# SMP.net
KiCad netlist of a schematic drawn in EAGLE
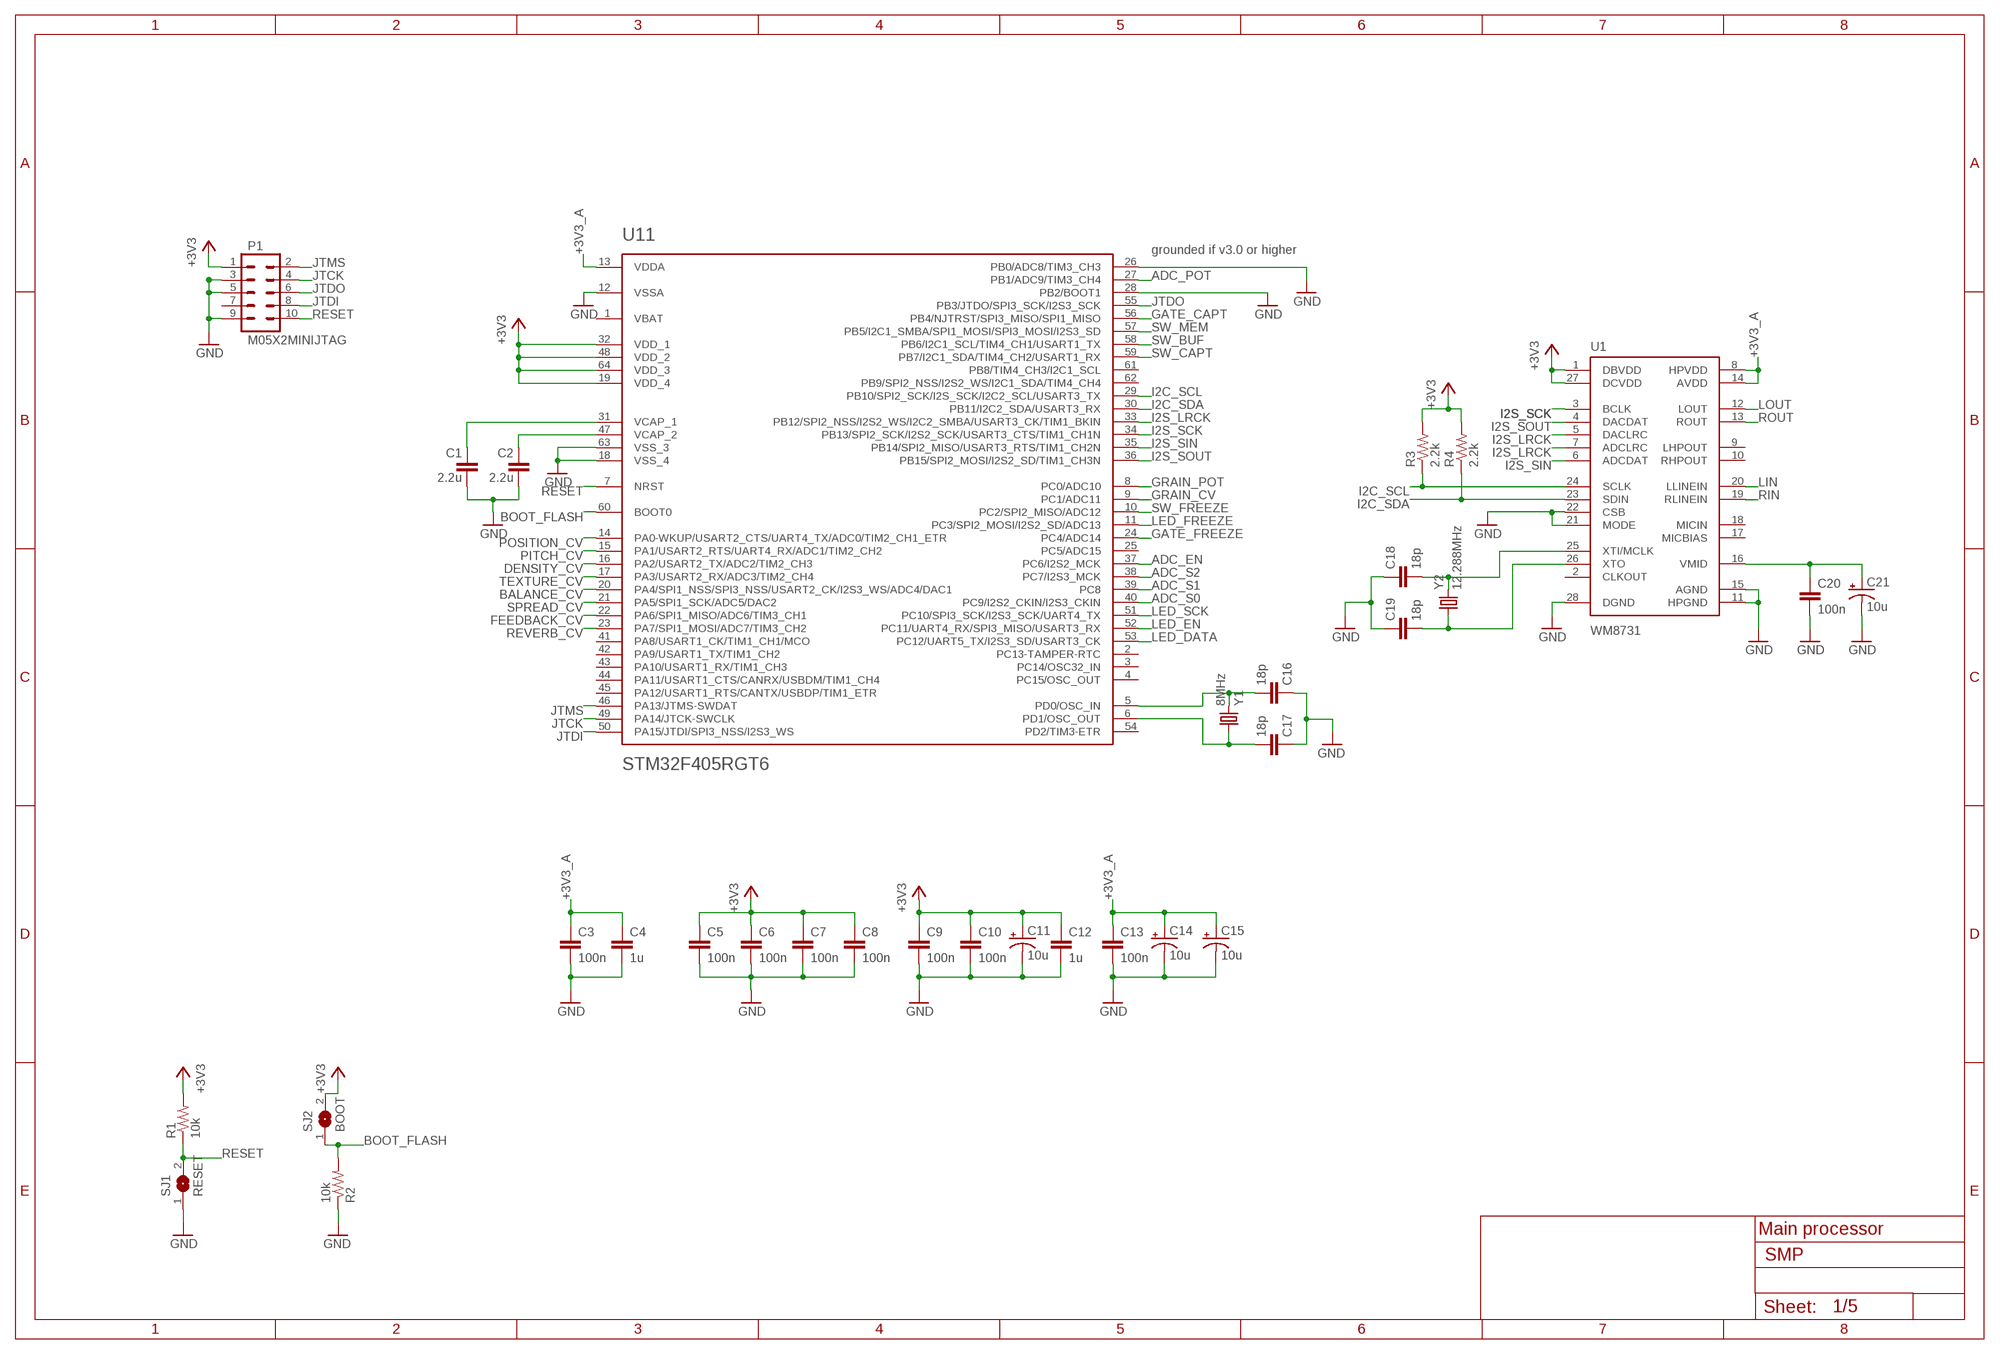
[diagram p0: schematic, sheet 1]
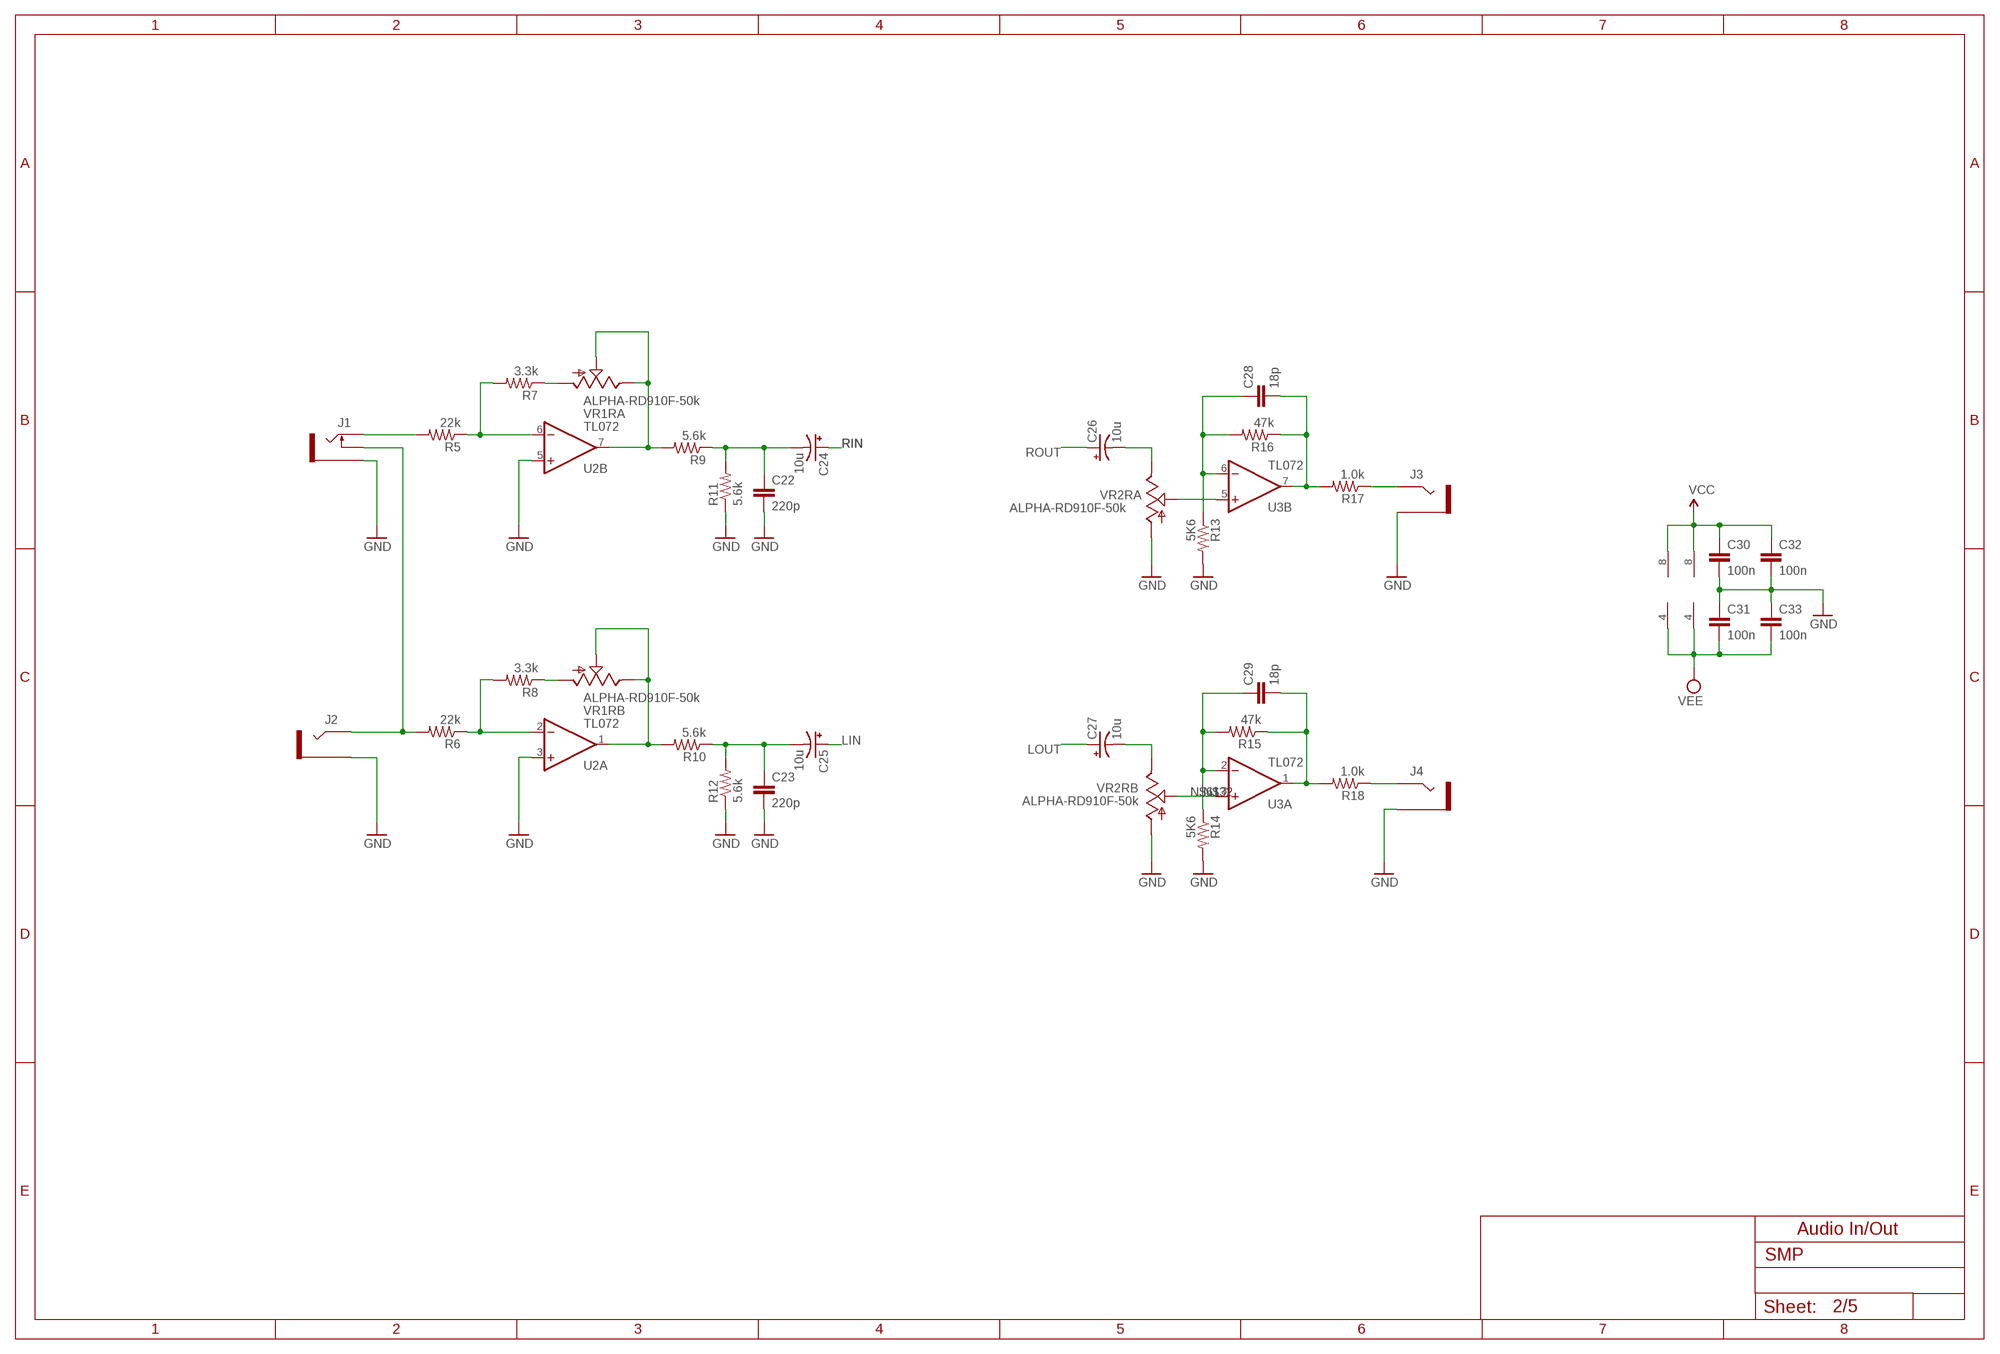
[diagram p1: schematic, sheet 2]
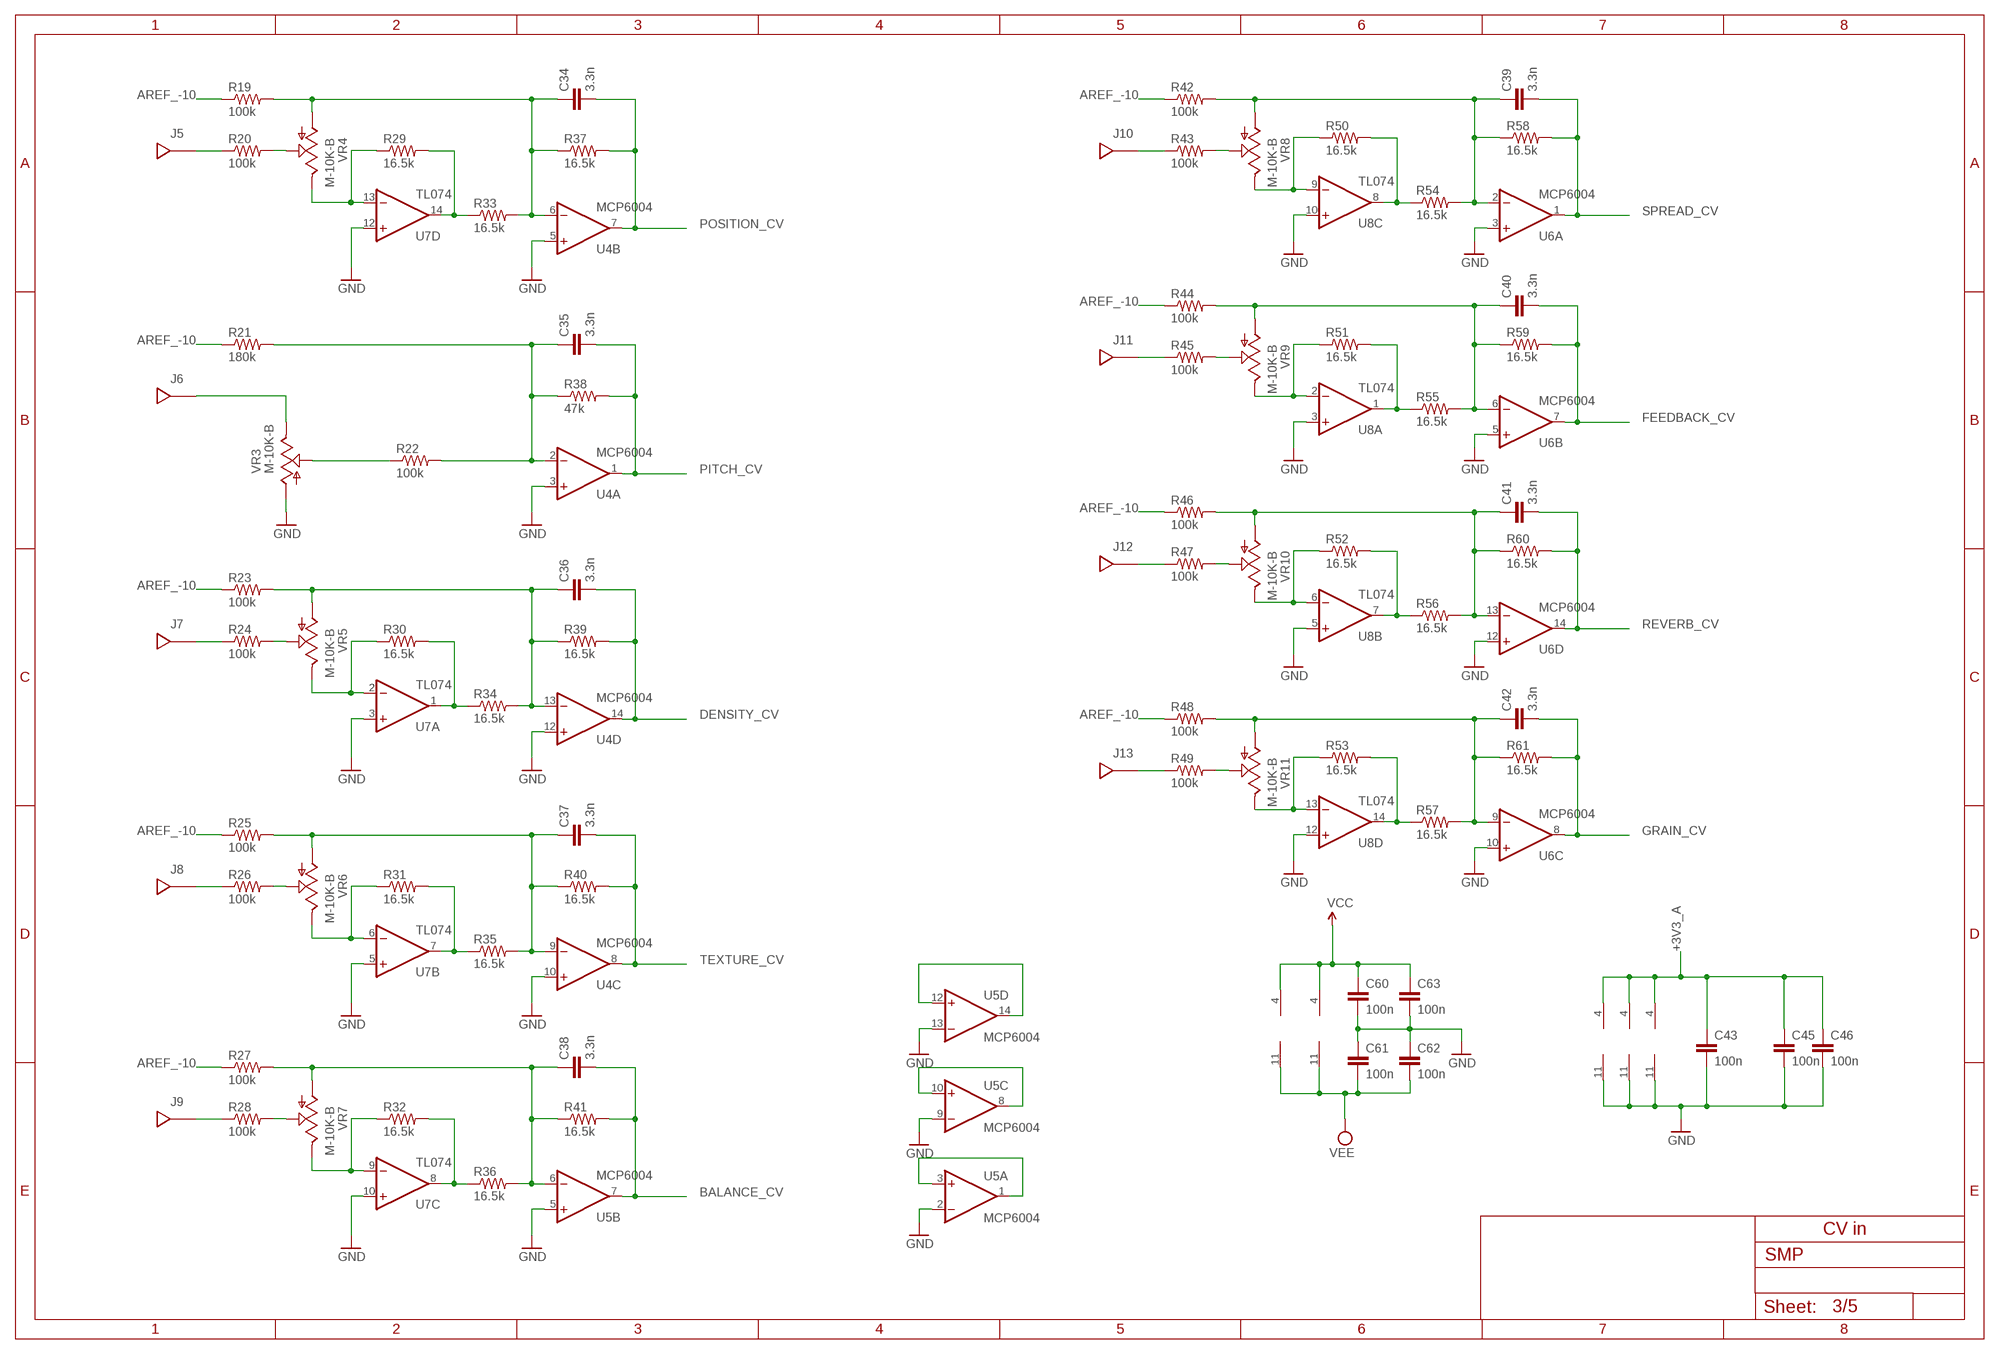
[diagram p2: schematic, sheet 3]
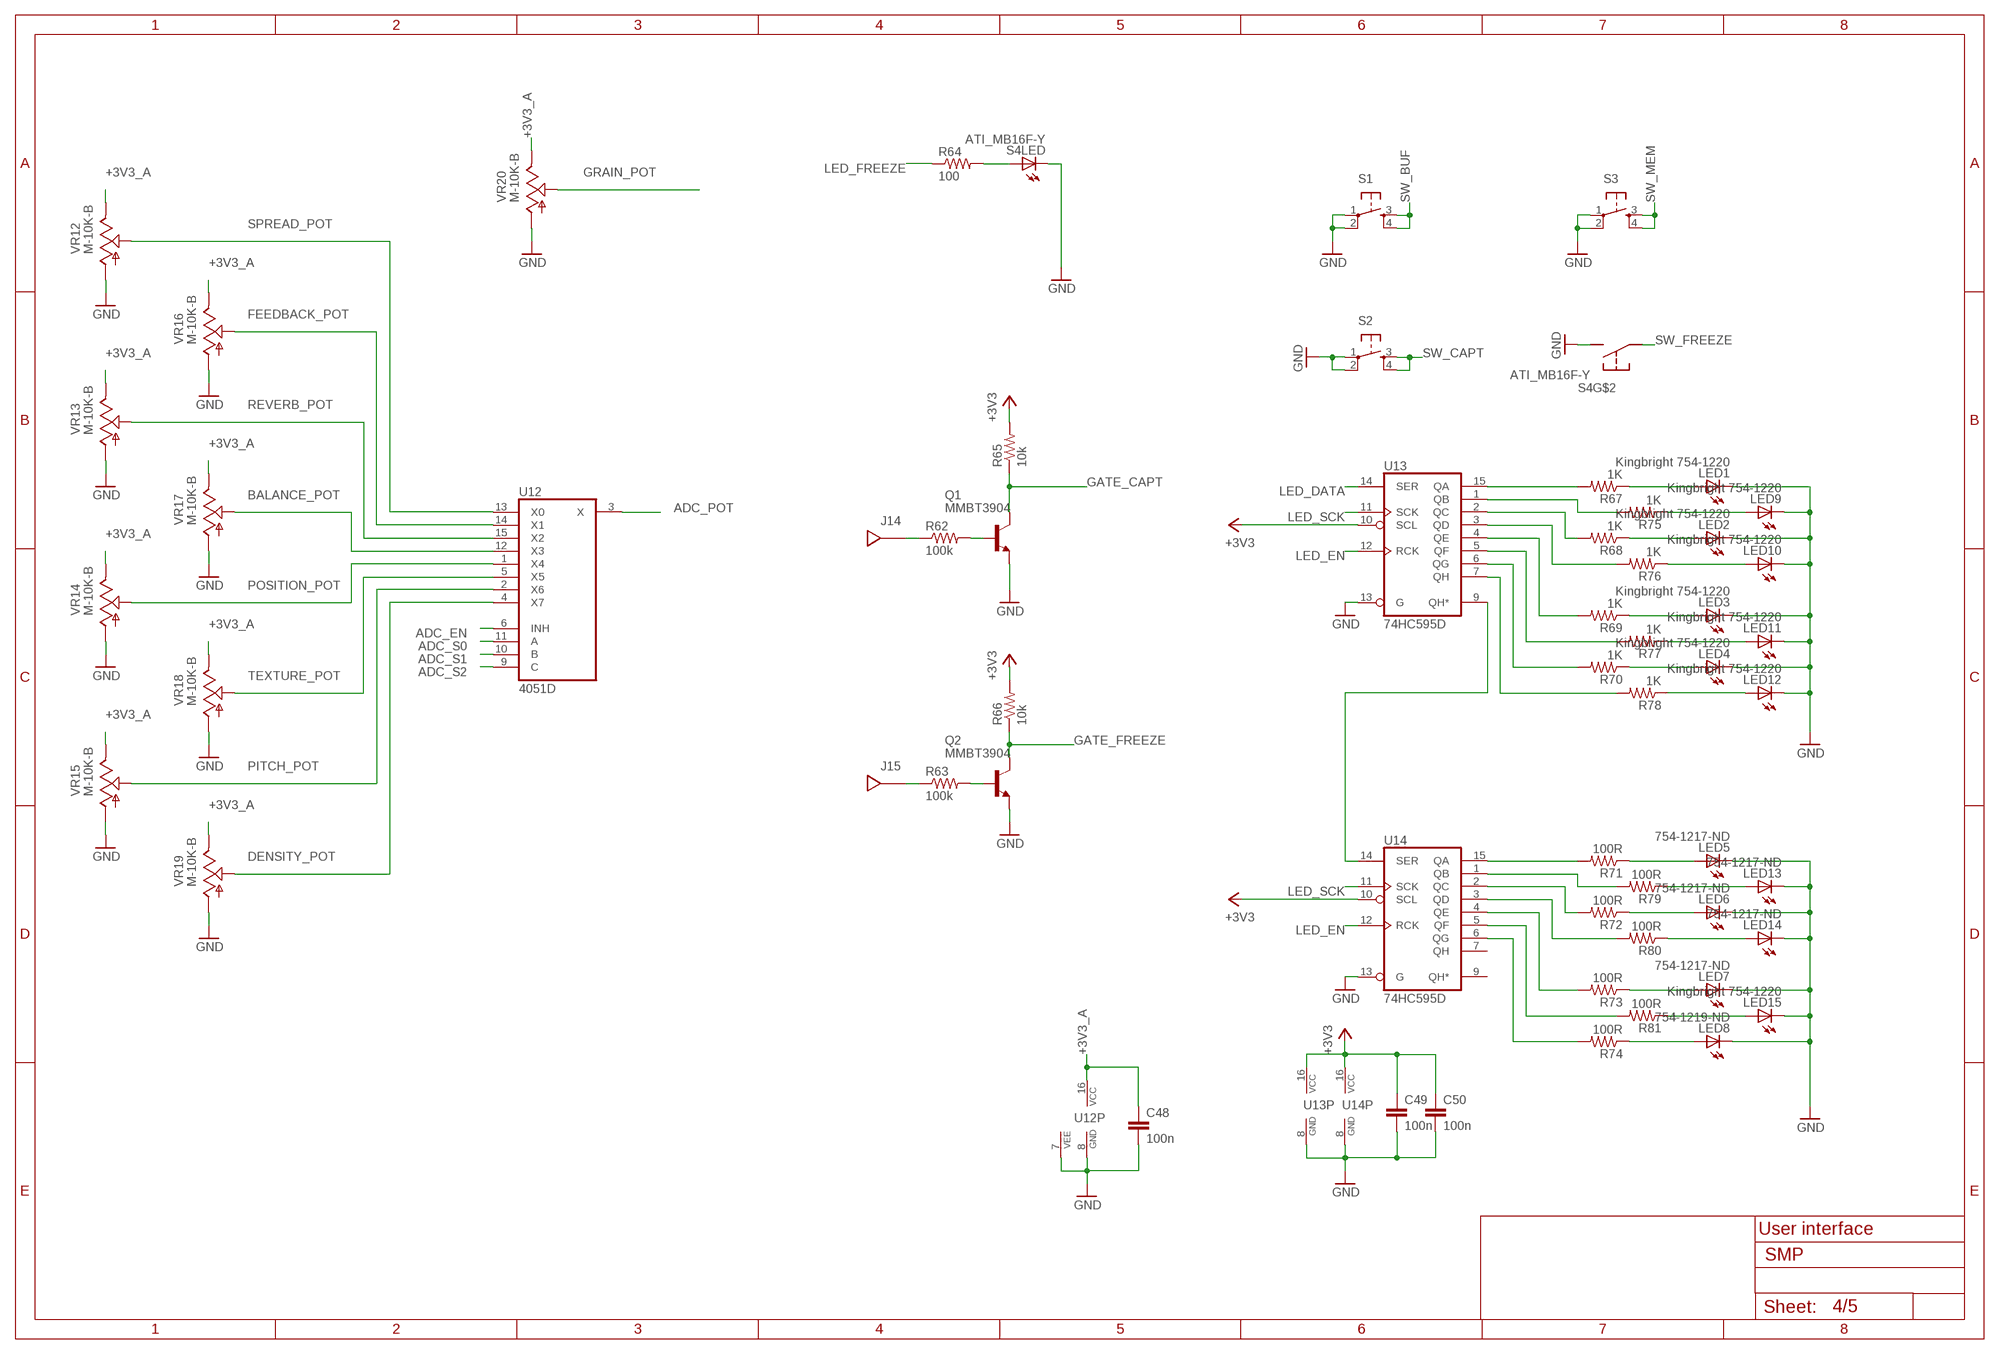
[diagram p3: schematic, sheet 4]
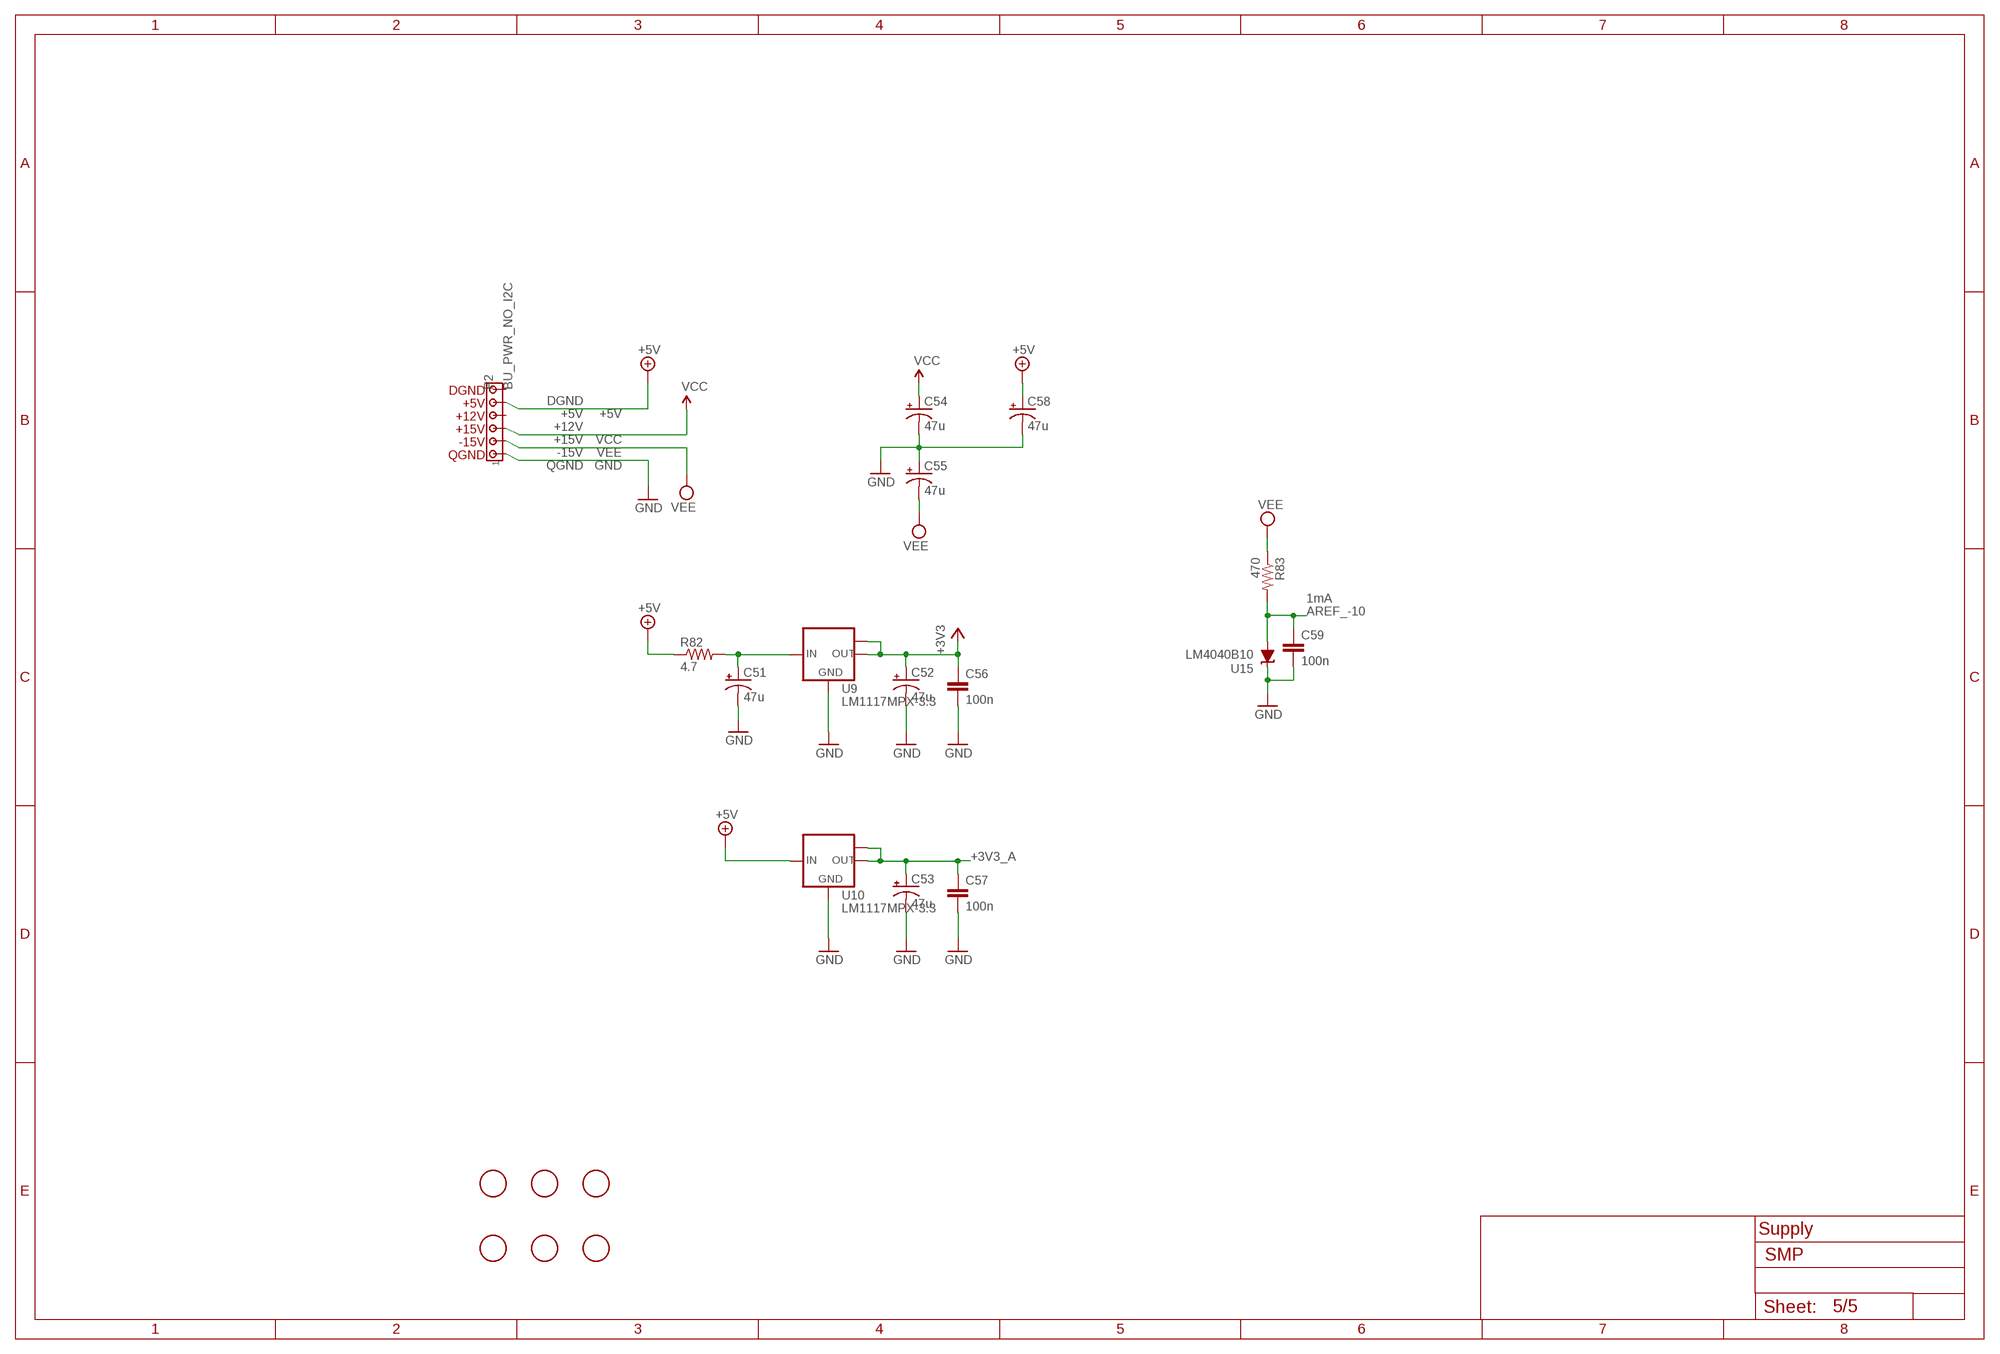
[diagram p4: schematic, sheet 5]

(export (version "E")
  (design (tool "Eeschema 10.0.6"))
  (components
    (comp (ref "C48")
      (value "100n")
      (footprint "eagle-import:C0603")
      (libsource (lib "eagle-import") (part "C-EUC0603"))
    )
    (comp (ref "C49")
      (value "100n")
      (footprint "eagle-import:C0603")
      (libsource (lib "eagle-import") (part "C-EUC0603"))
    )
    (comp (ref "C50")
      (value "100n")
      (footprint "eagle-import:C0603")
      (libsource (lib "eagle-import") (part "C-EUC0603"))
    )
    (comp (ref "J14")
      (value "JOHNSON_BANANASTD")
      (footprint "eagle-import:JOHNSON")
      (libsource (lib "eagle-import") (part "JOHNSON_BANANASTD"))
    )
    (comp (ref "J15")
      (value "JOHNSON_BANANASTD")
      (footprint "eagle-import:JOHNSON")
      (libsource (lib "eagle-import") (part "JOHNSON_BANANASTD"))
    )
    (comp (ref "LED1")
      (value "Kingbright 754-1220")
      (footprint "eagle-import:LED_3MM_MIN")
      (libsource (lib "eagle-import") (part "LED_3MM_MIN"))
    )
    (comp (ref "LED2")
      (value "Kingbright 754-1220")
      (footprint "eagle-import:LED_3MM_MIN")
      (libsource (lib "eagle-import") (part "LED_3MM_MIN"))
    )
    (comp (ref "LED3")
      (value "Kingbright 754-1220")
      (footprint "eagle-import:LED_3MM_MIN")
      (libsource (lib "eagle-import") (part "LED_3MM_MIN"))
    )
    (comp (ref "LED4")
      (value "Kingbright 754-1220")
      (footprint "eagle-import:LED_3MM_MIN")
      (libsource (lib "eagle-import") (part "LED_3MM_MIN"))
    )
    (comp (ref "LED5")
      (value "754-1217-ND")
      (footprint "eagle-import:LED_3MM_MIN")
      (libsource (lib "eagle-import") (part "LED_3MM_MIN"))
    )
    (comp (ref "LED6")
      (value "754-1217-ND")
      (footprint "eagle-import:LED_3MM_MIN")
      (libsource (lib "eagle-import") (part "LED_3MM_MIN"))
    )
    (comp (ref "LED7")
      (value "754-1217-ND")
      (footprint "eagle-import:LED_3MM_MIN")
      (libsource (lib "eagle-import") (part "LED_3MM_MIN"))
    )
    (comp (ref "LED8")
      (value "754-1219-ND")
      (footprint "eagle-import:LED_3MM_MIN")
      (libsource (lib "eagle-import") (part "LED_3MM_MIN"))
    )
    (comp (ref "LED9")
      (value "Kingbright 754-1220")
      (footprint "eagle-import:LED_3MM_MIN")
      (libsource (lib "eagle-import") (part "LED_3MM_MIN"))
    )
    (comp (ref "LED10")
      (value "Kingbright 754-1220")
      (footprint "eagle-import:LED_3MM_MIN")
      (libsource (lib "eagle-import") (part "LED_3MM_MIN"))
    )
    (comp (ref "LED11")
      (value "Kingbright 754-1220")
      (footprint "eagle-import:LED_3MM_MIN")
      (libsource (lib "eagle-import") (part "LED_3MM_MIN"))
    )
    (comp (ref "LED12")
      (value "Kingbright 754-1220")
      (footprint "eagle-import:LED_3MM_MIN")
      (libsource (lib "eagle-import") (part "LED_3MM_MIN"))
    )
    (comp (ref "LED13")
      (value "754-1217-ND")
      (footprint "eagle-import:LED_3MM_MIN")
      (libsource (lib "eagle-import") (part "LED_3MM_MIN"))
    )
    (comp (ref "LED14")
      (value "754-1217-ND")
      (footprint "eagle-import:LED_3MM_MIN")
      (libsource (lib "eagle-import") (part "LED_3MM_MIN"))
    )
    (comp (ref "LED15")
      (value "Kingbright 754-1220")
      (footprint "eagle-import:LED_3MM_MIN")
      (libsource (lib "eagle-import") (part "LED_3MM_MIN"))
    )
    (comp (ref "Q1")
      (value "MMBT3904")
      (footprint "eagle-import:SOT23-BEC")
      (libsource (lib "eagle-import") (part "-NPN-SOT23-BECMMBT3904LT1"))
    )
    (comp (ref "Q2")
      (value "MMBT3904")
      (footprint "eagle-import:SOT23-BEC")
      (libsource (lib "eagle-import") (part "-NPN-SOT23-BECMMBT3904LT1"))
    )
    (comp (ref "R62")
      (value "100k")
      (footprint "eagle-import:R0603")
      (libsource (lib "eagle-import") (part "R-US_R0603"))
    )
    (comp (ref "R63")
      (value "100k")
      (footprint "eagle-import:R0603")
      (libsource (lib "eagle-import") (part "R-US_R0603"))
    )
    (comp (ref "R64")
      (value "100")
      (footprint "eagle-import:R0603")
      (libsource (lib "eagle-import") (part "R-US_R0603"))
    )
    (comp (ref "R65")
      (value "10k")
      (footprint "eagle-import:R0603")
      (libsource (lib "eagle-import") (part "R-US_R0603"))
    )
    (comp (ref "R66")
      (value "10k")
      (footprint "eagle-import:R0603")
      (libsource (lib "eagle-import") (part "R-US_R0603"))
    )
    (comp (ref "R67")
      (value "1K")
      (footprint "eagle-import:R0603")
      (libsource (lib "eagle-import") (part "R-US_R0603"))
    )
    (comp (ref "R68")
      (value "1K")
      (footprint "eagle-import:R0603")
      (libsource (lib "eagle-import") (part "R-US_R0603"))
    )
    (comp (ref "R69")
      (value "1K")
      (footprint "eagle-import:R0603")
      (libsource (lib "eagle-import") (part "R-US_R0603"))
    )
    (comp (ref "R70")
      (value "1K")
      (footprint "eagle-import:R0603")
      (libsource (lib "eagle-import") (part "R-US_R0603"))
    )
    (comp (ref "R71")
      (value "100R")
      (footprint "eagle-import:R0603")
      (libsource (lib "eagle-import") (part "R-US_R0603"))
    )
    (comp (ref "R72")
      (value "100R")
      (footprint "eagle-import:R0603")
      (libsource (lib "eagle-import") (part "R-US_R0603"))
    )
    (comp (ref "R73")
      (value "100R")
      (footprint "eagle-import:R0603")
      (libsource (lib "eagle-import") (part "R-US_R0603"))
    )
    (comp (ref "R74")
      (value "100R")
      (footprint "eagle-import:R0603")
      (libsource (lib "eagle-import") (part "R-US_R0603"))
    )
    (comp (ref "R75")
      (value "1K")
      (footprint "eagle-import:R0603")
      (libsource (lib "eagle-import") (part "R-US_R0603"))
    )
    (comp (ref "R76")
      (value "1K")
      (footprint "eagle-import:R0603")
      (libsource (lib "eagle-import") (part "R-US_R0603"))
    )
    (comp (ref "R77")
      (value "1K")
      (footprint "eagle-import:R0603")
      (libsource (lib "eagle-import") (part "R-US_R0603"))
    )
    (comp (ref "R78")
      (value "1K")
      (footprint "eagle-import:R0603")
      (libsource (lib "eagle-import") (part "R-US_R0603"))
    )
    (comp (ref "R79")
      (value "100R")
      (footprint "eagle-import:R0603")
      (libsource (lib "eagle-import") (part "R-US_R0603"))
    )
    (comp (ref "R80")
      (value "100R")
      (footprint "eagle-import:R0603")
      (libsource (lib "eagle-import") (part "R-US_R0603"))
    )
    (comp (ref "R81")
      (value "100R")
      (footprint "eagle-import:R0603")
      (libsource (lib "eagle-import") (part "R-US_R0603"))
    )
    (comp (ref "S1")
      (value "TAC_SWITCH")
      (footprint "eagle-import:C&K_D6R")
      (libsource (lib "eagle-import") (part "TAC_SWITCH"))
    )
    (comp (ref "S2")
      (value "TAC_SWITCH")
      (footprint "eagle-import:C&K_D6R")
      (libsource (lib "eagle-import") (part "TAC_SWITCH"))
    )
    (comp (ref "S3")
      (value "TAC_SWITCH")
      (footprint "eagle-import:C&K_D6R")
      (libsource (lib "eagle-import") (part "TAC_SWITCH"))
    )
    (comp (ref "S4")
      (value "ATI_MB16F-Y")
      (footprint "eagle-import:MB16F")
      (libsource (lib "eagle-import") (part "ATI_MB16F-Y"))
    )
    (comp (ref "U12")
      (value "4051D")
      (footprint "eagle-import:SO16")
      (libsource (lib "eagle-import") (part "4051D"))
    )
    (comp (ref "U13")
      (value "74HC595D")
      (footprint "eagle-import:SO16")
      (libsource (lib "eagle-import") (part "74595DHC"))
    )
    (comp (ref "U14")
      (value "74HC595D")
      (footprint "eagle-import:SO16")
      (libsource (lib "eagle-import") (part "74595DHC"))
    )
    (comp (ref "VR12")
      (value "M-10K-B")
      (footprint "eagle-import:ALPHA901F")
      (libsource (lib "eagle-import") (part "POT_USRD901F"))
    )
    (comp (ref "VR13")
      (value "M-10K-B")
      (footprint "eagle-import:ALPHA901F")
      (libsource (lib "eagle-import") (part "POT_USRD901F"))
    )
    (comp (ref "VR14")
      (value "M-10K-B")
      (footprint "eagle-import:ALPHA901F")
      (libsource (lib "eagle-import") (part "POT_USRD901F"))
    )
    (comp (ref "VR15")
      (value "M-10K-B")
      (footprint "eagle-import:ALPHA901F")
      (libsource (lib "eagle-import") (part "POT_USRD901F"))
    )
    (comp (ref "VR16")
      (value "M-10K-B")
      (footprint "eagle-import:ALPHA901F")
      (libsource (lib "eagle-import") (part "POT_USRD901F"))
    )
    (comp (ref "VR17")
      (value "M-10K-B")
      (footprint "eagle-import:ALPHA901F")
      (libsource (lib "eagle-import") (part "POT_USRD901F"))
    )
    (comp (ref "VR18")
      (value "M-10K-B")
      (footprint "eagle-import:ALPHA901F")
      (libsource (lib "eagle-import") (part "POT_USRD901F"))
    )
    (comp (ref "VR19")
      (value "M-10K-B")
      (footprint "eagle-import:ALPHA901F")
      (libsource (lib "eagle-import") (part "POT_USRD901F"))
    )
    (comp (ref "VR20")
      (value "M-10K-B")
      (footprint "eagle-import:ALPHA901F")
      (libsource (lib "eagle-import") (part "POT_USRD901F"))
    )
    (comp (ref "C51")
      (value "47u")
      (footprint "eagle-import:PANASONIC_D")
      (libsource (lib "eagle-import") (part "CPOL-USD"))
    )
    (comp (ref "C52")
      (value "47u")
      (footprint "eagle-import:PANASONIC_D")
      (libsource (lib "eagle-import") (part "CPOL-USD"))
    )
    (comp (ref "C53")
      (value "47u")
      (footprint "eagle-import:PANASONIC_D")
      (libsource (lib "eagle-import") (part "CPOL-USD"))
    )
    (comp (ref "C54")
      (value "47u")
      (footprint "eagle-import:PANASONIC_D")
      (libsource (lib "eagle-import") (part "CPOL-USD"))
    )
    (comp (ref "C55")
      (value "47u")
      (footprint "eagle-import:PANASONIC_D")
      (libsource (lib "eagle-import") (part "CPOL-USD"))
    )
    (comp (ref "C56")
      (value "100n")
      (footprint "eagle-import:C0603")
      (libsource (lib "eagle-import") (part "C-EUC0603"))
    )
    (comp (ref "C57")
      (value "100n")
      (footprint "eagle-import:C0603")
      (libsource (lib "eagle-import") (part "C-EUC0603"))
    )
    (comp (ref "C58")
      (value "47u")
      (footprint "eagle-import:PANASONIC_D")
      (libsource (lib "eagle-import") (part "CPOL-USD"))
    )
    (comp (ref "C59")
      (value "100n")
      (footprint "eagle-import:C0603")
      (libsource (lib "eagle-import") (part "C-EUC0603"))
    )
    (comp (ref "FD1")
      (value "FIDUCIAL")
      (footprint "eagle-import:FIDUCIAL_1MM")
      (libsource (lib "eagle-import") (part "FIDUCIAL"))
    )
    (comp (ref "FD2")
      (value "FIDUCIAL")
      (footprint "eagle-import:FIDUCIAL_1MM")
      (libsource (lib "eagle-import") (part "FIDUCIAL"))
    )
    (comp (ref "FD3")
      (value "FIDUCIAL")
      (footprint "eagle-import:FIDUCIAL_1MM")
      (libsource (lib "eagle-import") (part "FIDUCIAL"))
    )
    (comp (ref "FD4")
      (value "FIDUCIAL")
      (footprint "eagle-import:FIDUCIAL_1MM")
      (libsource (lib "eagle-import") (part "FIDUCIAL"))
    )
    (comp (ref "FD5")
      (value "FIDUCIAL")
      (footprint "eagle-import:FIDUCIAL_1MM")
      (libsource (lib "eagle-import") (part "FIDUCIAL"))
    )
    (comp (ref "FD6")
      (value "FIDUCIAL")
      (footprint "eagle-import:FIDUCIAL_1MM")
      (libsource (lib "eagle-import") (part "FIDUCIAL"))
    )
    (comp (ref "P2")
      (value "BU_PWR_NO_I2C")
      (footprint "eagle-import:MTA_156")
      (libsource (lib "eagle-import") (part "BU_PWR_NO_I2C"))
    )
    (comp (ref "R82")
      (value "4.7")
      (footprint "eagle-import:R1206")
      (libsource (lib "eagle-import") (part "R-US_R1206"))
    )
    (comp (ref "R83")
      (value "470")
      (footprint "eagle-import:R0603")
      (libsource (lib "eagle-import") (part "R-US_R0603"))
    )
    (comp (ref "U9")
      (value "LM1117MPX-3.3")
      (footprint "eagle-import:SOT223")
      (libsource (lib "eagle-import") (part "LM1117MPX-3.3"))
    )
    (comp (ref "U10")
      (value "LM1117MPX-3.3")
      (footprint "eagle-import:SOT223")
      (libsource (lib "eagle-import") (part "LM1117MPX-3.3"))
    )
    (comp (ref "U15")
      (value "LM4040B10")
      (footprint "eagle-import:DBZ_R-PDSO-G3")
      (fields (field (name "MPN") "LM4041B12IDBZR"))
      (libsource (lib "eagle-import") (part "LM4041DBZB12"))
    )
    (comp (ref "C22")
      (value "220p")
      (footprint "eagle-import:C0603")
      (libsource (lib "eagle-import") (part "C-EUC0603"))
    )
    (comp (ref "C23")
      (value "220p")
      (footprint "eagle-import:C0603")
      (libsource (lib "eagle-import") (part "C-EUC0603"))
    )
    (comp (ref "C24")
      (value "10u")
      (footprint "eagle-import:PANASONIC_B")
      (libsource (lib "eagle-import") (part "CPOL-USB"))
    )
    (comp (ref "C25")
      (value "10u")
      (footprint "eagle-import:PANASONIC_B")
      (libsource (lib "eagle-import") (part "CPOL-USB"))
    )
    (comp (ref "C26")
      (value "10u")
      (footprint "eagle-import:PANASONIC_B")
      (libsource (lib "eagle-import") (part "CPOL-USB"))
    )
    (comp (ref "C27")
      (value "10u")
      (footprint "eagle-import:PANASONIC_B")
      (libsource (lib "eagle-import") (part "CPOL-USB"))
    )
    (comp (ref "C28")
      (value "18p")
      (footprint "eagle-import:C0603")
      (libsource (lib "eagle-import") (part "C-EUC0603"))
    )
    (comp (ref "C29")
      (value "18p")
      (footprint "eagle-import:C0603")
      (libsource (lib "eagle-import") (part "C-EUC0603"))
    )
    (comp (ref "C30")
      (value "100n")
      (footprint "eagle-import:C0603")
      (libsource (lib "eagle-import") (part "C-EUC0603"))
    )
    (comp (ref "C31")
      (value "100n")
      (footprint "eagle-import:C0603")
      (libsource (lib "eagle-import") (part "C-EUC0603"))
    )
    (comp (ref "C32")
      (value "100n")
      (footprint "eagle-import:C0603")
      (libsource (lib "eagle-import") (part "C-EUC0603"))
    )
    (comp (ref "C33")
      (value "100n")
      (footprint "eagle-import:C0603")
      (libsource (lib "eagle-import") (part "C-EUC0603"))
    )
    (comp (ref "J1")
      (value "SWITCHCRAFT_42A")
      (footprint "eagle-import:SWITCH_JOHNSON")
      (libsource (lib "eagle-import") (part "SWITCHCRAFT_42A"))
    )
    (comp (ref "J2")
      (value "SWITCHCRAFT_JACK")
      (footprint "eagle-import:SWITCH")
      (libsource (lib "eagle-import") (part "SWITCHCRAFT_JACK"))
    )
    (comp (ref "J3")
      (value "SWITCHCRAFT_JACK")
      (footprint "eagle-import:SWITCH")
      (libsource (lib "eagle-import") (part "SWITCHCRAFT_JACK"))
    )
    (comp (ref "J4")
      (value "SWITCHCRAFT_JACK")
      (footprint "eagle-import:SWITCH")
      (libsource (lib "eagle-import") (part "SWITCHCRAFT_JACK"))
    )
    (comp (ref "R5")
      (value "22k")
      (footprint "eagle-import:R0603")
      (libsource (lib "eagle-import") (part "R-US_R0603"))
    )
    (comp (ref "R6")
      (value "22k")
      (footprint "eagle-import:R0603")
      (libsource (lib "eagle-import") (part "R-US_R0603"))
    )
    (comp (ref "R7")
      (value "3.3k")
      (footprint "eagle-import:R0603")
      (libsource (lib "eagle-import") (part "R-US_R0603"))
    )
    (comp (ref "R8")
      (value "3.3k")
      (footprint "eagle-import:R0603")
      (libsource (lib "eagle-import") (part "R-US_R0603"))
    )
    (comp (ref "R9")
      (value "5.6k")
      (footprint "eagle-import:R0603")
      (libsource (lib "eagle-import") (part "R-US_R0603"))
    )
    (comp (ref "R10")
      (value "5.6k")
      (footprint "eagle-import:R0603")
      (libsource (lib "eagle-import") (part "R-US_R0603"))
    )
    (comp (ref "R11")
      (value "5.6k")
      (footprint "eagle-import:R0603")
      (libsource (lib "eagle-import") (part "R-US_R0603"))
    )
    (comp (ref "R12")
      (value "5.6k")
      (footprint "eagle-import:R0603")
      (libsource (lib "eagle-import") (part "R-US_R0603"))
    )
    (comp (ref "R13")
      (value "5K6")
      (footprint "eagle-import:R0603")
      (libsource (lib "eagle-import") (part "R-US_R0603"))
    )
    (comp (ref "R14")
      (value "5K6")
      (footprint "eagle-import:R0603")
      (libsource (lib "eagle-import") (part "R-US_R0603"))
    )
    (comp (ref "R15")
      (value "47k")
      (footprint "eagle-import:R0603")
      (libsource (lib "eagle-import") (part "R-US_R0603"))
    )
    (comp (ref "R16")
      (value "47k")
      (footprint "eagle-import:R0603")
      (libsource (lib "eagle-import") (part "R-US_R0603"))
    )
    (comp (ref "R17")
      (value "1.0k")
      (footprint "eagle-import:R0603")
      (libsource (lib "eagle-import") (part "R-US_R0603"))
    )
    (comp (ref "R18")
      (value "1.0k")
      (footprint "eagle-import:R0603")
      (libsource (lib "eagle-import") (part "R-US_R0603"))
    )
    (comp (ref "U2")
      (value "TL072")
      (footprint "eagle-import:SO08")
      (libsource (lib "eagle-import") (part "DUAL_OPAMPD"))
    )
    (comp (ref "U3")
      (value "TL072")
      (footprint "eagle-import:SO08")
      (libsource (lib "eagle-import") (part "DUAL_OPAMPD"))
    )
    (comp (ref "VR1")
      (value "ALPHA-RD910F-50k")
      (footprint "eagle-import:ALPHA902F")
      (libsource (lib "eagle-import") (part "POT_US_DUAL_GANGALPHA"))
    )
    (comp (ref "VR2")
      (value "ALPHA-RD910F-50k")
      (footprint "eagle-import:ALPHA902F")
      (libsource (lib "eagle-import") (part "POT_US_DUAL_GANGALPHA"))
    )
    (comp (ref "C34")
      (value "3.3n")
      (footprint "eagle-import:C0603")
      (libsource (lib "eagle-import") (part "C-EUC0603"))
    )
    (comp (ref "C35")
      (value "3.3n")
      (footprint "eagle-import:C0603")
      (libsource (lib "eagle-import") (part "C-EUC0603"))
    )
    (comp (ref "C36")
      (value "3.3n")
      (footprint "eagle-import:C0603")
      (libsource (lib "eagle-import") (part "C-EUC0603"))
    )
    (comp (ref "C37")
      (value "3.3n")
      (footprint "eagle-import:C0603")
      (libsource (lib "eagle-import") (part "C-EUC0603"))
    )
    (comp (ref "C38")
      (value "3.3n")
      (footprint "eagle-import:C0603")
      (libsource (lib "eagle-import") (part "C-EUC0603"))
    )
    (comp (ref "C39")
      (value "3.3n")
      (footprint "eagle-import:C0603")
      (libsource (lib "eagle-import") (part "C-EUC0603"))
    )
    (comp (ref "C40")
      (value "3.3n")
      (footprint "eagle-import:C0603")
      (libsource (lib "eagle-import") (part "C-EUC0603"))
    )
    (comp (ref "C41")
      (value "3.3n")
      (footprint "eagle-import:C0603")
      (libsource (lib "eagle-import") (part "C-EUC0603"))
    )
    (comp (ref "C42")
      (value "3.3n")
      (footprint "eagle-import:C0603")
      (libsource (lib "eagle-import") (part "C-EUC0603"))
    )
    (comp (ref "C43")
      (value "100n")
      (footprint "eagle-import:C0603")
      (libsource (lib "eagle-import") (part "C-EUC0603"))
    )
    (comp (ref "C45")
      (value "100n")
      (footprint "eagle-import:C0603")
      (libsource (lib "eagle-import") (part "C-EUC0603"))
    )
    (comp (ref "C46")
      (value "100n")
      (footprint "eagle-import:C0603")
      (libsource (lib "eagle-import") (part "C-EUC0603"))
    )
    (comp (ref "C60")
      (value "100n")
      (footprint "eagle-import:C0603")
      (libsource (lib "eagle-import") (part "C-EUC0603"))
    )
    (comp (ref "C61")
      (value "100n")
      (footprint "eagle-import:C0603")
      (libsource (lib "eagle-import") (part "C-EUC0603"))
    )
    (comp (ref "C62")
      (value "100n")
      (footprint "eagle-import:C0603")
      (libsource (lib "eagle-import") (part "C-EUC0603"))
    )
    (comp (ref "C63")
      (value "100n")
      (footprint "eagle-import:C0603")
      (libsource (lib "eagle-import") (part "C-EUC0603"))
    )
    (comp (ref "J5")
      (value "JOHNSON_BANANASTD")
      (footprint "eagle-import:JOHNSON")
      (libsource (lib "eagle-import") (part "JOHNSON_BANANASTD"))
    )
    (comp (ref "J6")
      (value "JOHNSON_BANANASTD")
      (footprint "eagle-import:JOHNSON")
      (libsource (lib "eagle-import") (part "JOHNSON_BANANASTD"))
    )
    (comp (ref "J7")
      (value "JOHNSON_BANANASTD")
      (footprint "eagle-import:JOHNSON")
      (libsource (lib "eagle-import") (part "JOHNSON_BANANASTD"))
    )
    (comp (ref "J8")
      (value "JOHNSON_BANANASTD")
      (footprint "eagle-import:JOHNSON")
      (libsource (lib "eagle-import") (part "JOHNSON_BANANASTD"))
    )
    (comp (ref "J9")
      (value "JOHNSON_BANANASTD")
      (footprint "eagle-import:JOHNSON")
      (libsource (lib "eagle-import") (part "JOHNSON_BANANASTD"))
    )
    (comp (ref "J10")
      (value "JOHNSON_BANANASTD")
      (footprint "eagle-import:JOHNSON")
      (libsource (lib "eagle-import") (part "JOHNSON_BANANASTD"))
    )
    (comp (ref "J11")
      (value "JOHNSON_BANANASTD")
      (footprint "eagle-import:JOHNSON")
      (libsource (lib "eagle-import") (part "JOHNSON_BANANASTD"))
    )
    (comp (ref "J12")
      (value "JOHNSON_BANANASTD")
      (footprint "eagle-import:JOHNSON")
      (libsource (lib "eagle-import") (part "JOHNSON_BANANASTD"))
    )
    (comp (ref "J13")
      (value "JOHNSON_BANANASTD")
      (footprint "eagle-import:JOHNSON")
      (libsource (lib "eagle-import") (part "JOHNSON_BANANASTD"))
    )
    (comp (ref "R19")
      (value "100k")
      (footprint "eagle-import:R0603")
      (libsource (lib "eagle-import") (part "R-US_R0603"))
    )
    (comp (ref "R20")
      (value "100k")
      (footprint "eagle-import:R0603")
      (libsource (lib "eagle-import") (part "R-US_R0603"))
    )
    (comp (ref "R21")
      (value "180k")
      (footprint "eagle-import:R0603")
      (libsource (lib "eagle-import") (part "R-US_R0603"))
    )
    (comp (ref "R22")
      (value "100k")
      (footprint "eagle-import:R0603")
      (libsource (lib "eagle-import") (part "R-US_R0603"))
    )
    (comp (ref "R23")
      (value "100k")
      (footprint "eagle-import:R0603")
      (libsource (lib "eagle-import") (part "R-US_R0603"))
    )
    (comp (ref "R24")
      (value "100k")
      (footprint "eagle-import:R0603")
      (libsource (lib "eagle-import") (part "R-US_R0603"))
    )
    (comp (ref "R25")
      (value "100k")
      (footprint "eagle-import:R0603")
      (libsource (lib "eagle-import") (part "R-US_R0603"))
    )
    (comp (ref "R26")
      (value "100k")
      (footprint "eagle-import:R0603")
      (libsource (lib "eagle-import") (part "R-US_R0603"))
    )
    (comp (ref "R27")
      (value "100k")
      (footprint "eagle-import:R0603")
      (libsource (lib "eagle-import") (part "R-US_R0603"))
    )
    (comp (ref "R28")
      (value "100k")
      (footprint "eagle-import:R0603")
      (libsource (lib "eagle-import") (part "R-US_R0603"))
    )
    (comp (ref "R29")
      (value "16.5k")
      (footprint "eagle-import:R0603")
      (libsource (lib "eagle-import") (part "R-US_R0603"))
    )
    (comp (ref "R30")
      (value "16.5k")
      (footprint "eagle-import:R0603")
      (libsource (lib "eagle-import") (part "R-US_R0603"))
    )
    (comp (ref "R31")
      (value "16.5k")
      (footprint "eagle-import:R0603")
      (libsource (lib "eagle-import") (part "R-US_R0603"))
    )
    (comp (ref "R32")
      (value "16.5k")
      (footprint "eagle-import:R0603")
      (libsource (lib "eagle-import") (part "R-US_R0603"))
    )
    (comp (ref "R33")
      (value "16.5k")
      (footprint "eagle-import:R0603")
      (libsource (lib "eagle-import") (part "R-US_R0603"))
    )
    (comp (ref "R34")
      (value "16.5k")
      (footprint "eagle-import:R0603")
      (libsource (lib "eagle-import") (part "R-US_R0603"))
    )
    (comp (ref "R35")
      (value "16.5k")
      (footprint "eagle-import:R0603")
      (libsource (lib "eagle-import") (part "R-US_R0603"))
    )
    (comp (ref "R36")
      (value "16.5k")
      (footprint "eagle-import:R0603")
      (libsource (lib "eagle-import") (part "R-US_R0603"))
    )
    (comp (ref "R37")
      (value "16.5k")
      (footprint "eagle-import:R0603")
      (libsource (lib "eagle-import") (part "R-US_R0603"))
    )
    (comp (ref "R38")
      (value "47k")
      (footprint "eagle-import:R0603")
      (libsource (lib "eagle-import") (part "R-US_R0603"))
    )
    (comp (ref "R39")
      (value "16.5k")
      (footprint "eagle-import:R0603")
      (libsource (lib "eagle-import") (part "R-US_R0603"))
    )
    (comp (ref "R40")
      (value "16.5k")
      (footprint "eagle-import:R0603")
      (libsource (lib "eagle-import") (part "R-US_R0603"))
    )
    (comp (ref "R41")
      (value "16.5k")
      (footprint "eagle-import:R0603")
      (libsource (lib "eagle-import") (part "R-US_R0603"))
    )
    (comp (ref "R42")
      (value "100k")
      (footprint "eagle-import:R0603")
      (libsource (lib "eagle-import") (part "R-US_R0603"))
    )
    (comp (ref "R43")
      (value "100k")
      (footprint "eagle-import:R0603")
      (libsource (lib "eagle-import") (part "R-US_R0603"))
    )
    (comp (ref "R44")
      (value "100k")
      (footprint "eagle-import:R0603")
      (libsource (lib "eagle-import") (part "R-US_R0603"))
    )
    (comp (ref "R45")
      (value "100k")
      (footprint "eagle-import:R0603")
      (libsource (lib "eagle-import") (part "R-US_R0603"))
    )
    (comp (ref "R46")
      (value "100k")
      (footprint "eagle-import:R0603")
      (libsource (lib "eagle-import") (part "R-US_R0603"))
    )
    (comp (ref "R47")
      (value "100k")
      (footprint "eagle-import:R0603")
      (libsource (lib "eagle-import") (part "R-US_R0603"))
    )
    (comp (ref "R48")
      (value "100k")
      (footprint "eagle-import:R0603")
      (libsource (lib "eagle-import") (part "R-US_R0603"))
    )
    (comp (ref "R49")
      (value "100k")
      (footprint "eagle-import:R0603")
      (libsource (lib "eagle-import") (part "R-US_R0603"))
    )
    (comp (ref "R50")
      (value "16.5k")
      (footprint "eagle-import:R0603")
      (libsource (lib "eagle-import") (part "R-US_R0603"))
    )
    (comp (ref "R51")
      (value "16.5k")
      (footprint "eagle-import:R0603")
      (libsource (lib "eagle-import") (part "R-US_R0603"))
    )
    (comp (ref "R52")
      (value "16.5k")
      (footprint "eagle-import:R0603")
      (libsource (lib "eagle-import") (part "R-US_R0603"))
    )
    (comp (ref "R53")
      (value "16.5k")
      (footprint "eagle-import:R0603")
      (libsource (lib "eagle-import") (part "R-US_R0603"))
    )
    (comp (ref "R54")
      (value "16.5k")
      (footprint "eagle-import:R0603")
      (libsource (lib "eagle-import") (part "R-US_R0603"))
    )
    (comp (ref "R55")
      (value "16.5k")
      (footprint "eagle-import:R0603")
      (libsource (lib "eagle-import") (part "R-US_R0603"))
    )
    (comp (ref "R56")
      (value "16.5k")
      (footprint "eagle-import:R0603")
      (libsource (lib "eagle-import") (part "R-US_R0603"))
    )
    (comp (ref "R57")
      (value "16.5k")
      (footprint "eagle-import:R0603")
      (libsource (lib "eagle-import") (part "R-US_R0603"))
    )
    (comp (ref "R58")
      (value "16.5k")
      (footprint "eagle-import:R0603")
      (libsource (lib "eagle-import") (part "R-US_R0603"))
    )
    (comp (ref "R59")
      (value "16.5k")
      (footprint "eagle-import:R0603")
      (libsource (lib "eagle-import") (part "R-US_R0603"))
    )
    (comp (ref "R60")
      (value "16.5k")
      (footprint "eagle-import:R0603")
      (libsource (lib "eagle-import") (part "R-US_R0603"))
    )
    (comp (ref "R61")
      (value "16.5k")
      (footprint "eagle-import:R0603")
      (libsource (lib "eagle-import") (part "R-US_R0603"))
    )
    (comp (ref "U4")
      (value "MCP6004")
      (footprint "eagle-import:SO14")
      (libsource (lib "eagle-import") (part "QUAD_OPAMPD"))
    )
    (comp (ref "U5")
      (value "MCP6004")
      (footprint "eagle-import:SO14")
      (libsource (lib "eagle-import") (part "QUAD_OPAMPD"))
    )
    (comp (ref "U6")
      (value "MCP6004")
      (footprint "eagle-import:SO14")
      (libsource (lib "eagle-import") (part "QUAD_OPAMPD"))
    )
    (comp (ref "U7")
      (value "TL074")
      (footprint "eagle-import:SO14")
      (libsource (lib "eagle-import") (part "QUAD_OPAMPD"))
    )
    (comp (ref "U8")
      (value "TL074")
      (footprint "eagle-import:SO14")
      (libsource (lib "eagle-import") (part "QUAD_OPAMPD"))
    )
    (comp (ref "VR3")
      (value "M-10K-B")
      (footprint "eagle-import:ALPHA901F")
      (libsource (lib "eagle-import") (part "POT_USRD901F"))
    )
    (comp (ref "VR4")
      (value "M-10K-B")
      (footprint "eagle-import:ALPHA901F")
      (libsource (lib "eagle-import") (part "POT_USRD901F"))
    )
    (comp (ref "VR5")
      (value "M-10K-B")
      (footprint "eagle-import:ALPHA901F")
      (libsource (lib "eagle-import") (part "POT_USRD901F"))
    )
    (comp (ref "VR6")
      (value "M-10K-B")
      (footprint "eagle-import:ALPHA901F")
      (libsource (lib "eagle-import") (part "POT_USRD901F"))
    )
    (comp (ref "VR7")
      (value "M-10K-B")
      (footprint "eagle-import:ALPHA901F")
      (libsource (lib "eagle-import") (part "POT_USRD901F"))
    )
    (comp (ref "VR8")
      (value "M-10K-B")
      (footprint "eagle-import:ALPHA901F")
      (libsource (lib "eagle-import") (part "POT_USRD901F"))
    )
    (comp (ref "VR9")
      (value "M-10K-B")
      (footprint "eagle-import:ALPHA901F")
      (libsource (lib "eagle-import") (part "POT_USRD901F"))
    )
    (comp (ref "VR10")
      (value "M-10K-B")
      (footprint "eagle-import:ALPHA901F")
      (libsource (lib "eagle-import") (part "POT_USRD901F"))
    )
    (comp (ref "VR11")
      (value "M-10K-B")
      (footprint "eagle-import:ALPHA901F")
      (libsource (lib "eagle-import") (part "POT_USRD901F"))
    )
    (comp (ref "C1")
      (value "2.2u")
      (footprint "eagle-import:C0603")
      (libsource (lib "eagle-import") (part "C-EUC0603"))
    )
    (comp (ref "C2")
      (value "2.2u")
      (footprint "eagle-import:C0603")
      (libsource (lib "eagle-import") (part "C-EUC0603"))
    )
    (comp (ref "C3")
      (value "100n")
      (footprint "eagle-import:C0603")
      (libsource (lib "eagle-import") (part "C-EUC0603"))
    )
    (comp (ref "C4")
      (value "1u")
      (footprint "eagle-import:C0603")
      (libsource (lib "eagle-import") (part "C-EUC0603"))
    )
    (comp (ref "C5")
      (value "100n")
      (footprint "eagle-import:C0603")
      (libsource (lib "eagle-import") (part "C-EUC0603"))
    )
    (comp (ref "C6")
      (value "100n")
      (footprint "eagle-import:C0603")
      (libsource (lib "eagle-import") (part "C-EUC0603"))
    )
    (comp (ref "C7")
      (value "100n")
      (footprint "eagle-import:C0603")
      (libsource (lib "eagle-import") (part "C-EUC0603"))
    )
    (comp (ref "C8")
      (value "100n")
      (footprint "eagle-import:C0603")
      (libsource (lib "eagle-import") (part "C-EUC0603"))
    )
    (comp (ref "C9")
      (value "100n")
      (footprint "eagle-import:C0603")
      (libsource (lib "eagle-import") (part "C-EUC0603"))
    )
    (comp (ref "C10")
      (value "100n")
      (footprint "eagle-import:C0603")
      (libsource (lib "eagle-import") (part "C-EUC0603"))
    )
    (comp (ref "C11")
      (value "10u")
      (footprint "eagle-import:PANASONIC_A")
      (libsource (lib "eagle-import") (part "CPOL-USA"))
    )
    (comp (ref "C12")
      (value "1u")
      (footprint "eagle-import:C0603")
      (libsource (lib "eagle-import") (part "C-EUC0603"))
    )
    (comp (ref "C13")
      (value "100n")
      (footprint "eagle-import:C0603")
      (libsource (lib "eagle-import") (part "C-EUC0603"))
    )
    (comp (ref "C14")
      (value "10u")
      (footprint "eagle-import:PANASONIC_A")
      (libsource (lib "eagle-import") (part "CPOL-USA"))
    )
    (comp (ref "C15")
      (value "10u")
      (footprint "eagle-import:PANASONIC_B")
      (libsource (lib "eagle-import") (part "CPOL-USB"))
    )
    (comp (ref "C16")
      (value "18p")
      (footprint "eagle-import:C0603")
      (libsource (lib "eagle-import") (part "C-EUC0603"))
    )
    (comp (ref "C17")
      (value "18p")
      (footprint "eagle-import:C0603")
      (libsource (lib "eagle-import") (part "C-EUC0603"))
    )
    (comp (ref "C18")
      (value "18p")
      (footprint "eagle-import:C0603")
      (libsource (lib "eagle-import") (part "C-EUC0603"))
    )
    (comp (ref "C19")
      (value "18p")
      (footprint "eagle-import:C0603")
      (libsource (lib "eagle-import") (part "C-EUC0603"))
    )
    (comp (ref "C20")
      (value "100n")
      (footprint "eagle-import:C0603")
      (libsource (lib "eagle-import") (part "C-EUC0603"))
    )
    (comp (ref "C21")
      (value "10u")
      (footprint "eagle-import:PANASONIC_B")
      (libsource (lib "eagle-import") (part "CPOL-USB"))
    )
    (comp (ref "P1")
      (value "M05X2MINIJTAG")
      (footprint "eagle-import:2X5-1.27")
      (libsource (lib "eagle-import") (part "M05X2MINIJTAG"))
    )
    (comp (ref "R1")
      (value "10k")
      (footprint "eagle-import:R0603")
      (libsource (lib "eagle-import") (part "R-US_R0603"))
    )
    (comp (ref "R2")
      (value "10k")
      (footprint "eagle-import:R0603")
      (libsource (lib "eagle-import") (part "R-US_R0603"))
    )
    (comp (ref "R3")
      (value "2.2k")
      (footprint "eagle-import:R0603")
      (libsource (lib "eagle-import") (part "R-US_R0603"))
    )
    (comp (ref "R4")
      (value "2.2k")
      (footprint "eagle-import:R0603")
      (libsource (lib "eagle-import") (part "R-US_R0603"))
    )
    (comp (ref "SJ1")
      (value "RESET")
      (footprint "eagle-import:SJ")
      (libsource (lib "eagle-import") (part "SJ"))
    )
    (comp (ref "SJ2")
      (value "BOOT")
      (footprint "eagle-import:SJ")
      (libsource (lib "eagle-import") (part "SJ"))
    )
    (comp (ref "U1")
      (value "WM8731")
      (footprint "eagle-import:SSOP28")
      (libsource (lib "eagle-import") (part "WM8731"))
    )
    (comp (ref "U11")
      (value "STM32F405RGT6")
      (footprint "eagle-import:TQFP-10X10-64")
      (libsource (lib "eagle-import") (part "STM32F20X"))
    )
    (comp (ref "Y1")
      (value "8MHz")
      (footprint "eagle-import:HC49UP")
      (libsource (lib "eagle-import") (part "CRYSTALHC49UP"))
    )
    (comp (ref "Y2")
      (value "12.288MHz")
      (footprint "eagle-import:HC49UP")
      (libsource (lib "eagle-import") (part "CRYSTALHC49UP"))
    )
  )
  (nets
    (net (code "1") (name "+3V3") (class "Default")
      (node (ref "C10") (pin "1") (pinfunction "1_1") (pintype "passive"))
      (node (ref "C11") (pin "+") (pinfunction "+_+") (pintype "passive"))
      (node (ref "C12") (pin "1") (pinfunction "1_1") (pintype "passive"))
      (node (ref "C49") (pin "1") (pinfunction "1_1") (pintype "passive"))
      (node (ref "C5") (pin "1") (pinfunction "1_1") (pintype "passive"))
      (node (ref "C50") (pin "1") (pinfunction "1_1") (pintype "passive"))
      (node (ref "C52") (pin "+") (pinfunction "+_+") (pintype "passive"))
      (node (ref "C56") (pin "1") (pinfunction "1_1") (pintype "passive"))
      (node (ref "C6") (pin "1") (pinfunction "1_1") (pintype "passive"))
      (node (ref "C7") (pin "1") (pinfunction "1_1") (pintype "passive"))
      (node (ref "C8") (pin "1") (pinfunction "1_1") (pintype "passive"))
      (node (ref "C9") (pin "1") (pinfunction "1_1") (pintype "passive"))
      (node (ref "P1") (pin "1") (pinfunction "1_1") (pintype "passive"))
      (node (ref "R1") (pin "2") (pinfunction "2_2") (pintype "passive"))
      (node (ref "R3") (pin "2") (pinfunction "2_2") (pintype "passive"))
      (node (ref "R4") (pin "2") (pinfunction "2_2") (pintype "passive"))
      (node (ref "R65") (pin "2") (pinfunction "2_2") (pintype "passive"))
      (node (ref "R66") (pin "2") (pinfunction "2_2") (pintype "passive"))
      (node (ref "SJ2") (pin "2") (pinfunction "2_2") (pintype "passive"))
      (node (ref "U1") (pin "1") (pinfunction "DBVDD_1") (pintype "bidirectional"))
      (node (ref "U1") (pin "27") (pinfunction "DCVDD_27") (pintype "bidirectional"))
      (node (ref "U11") (pin "19") (pinfunction "VDD_4_19") (pintype "power_in"))
      (node (ref "U11") (pin "32") (pinfunction "VDD_1_32") (pintype "power_in"))
      (node (ref "U11") (pin "48") (pinfunction "VDD_2_48") (pintype "power_in"))
      (node (ref "U11") (pin "64") (pinfunction "VDD_3_64") (pintype "power_in"))
      (node (ref "U13") (pin "10") (pinfunction "SCL_10") (pintype "input"))
      (node (ref "U13") (pin "16") (pinfunction "VCC_16") (pintype "power_in"))
      (node (ref "U14") (pin "10") (pinfunction "SCL_10") (pintype "input"))
      (node (ref "U14") (pin "16") (pinfunction "VCC_16") (pintype "power_in"))
      (node (ref "U9") (pin "2") (pinfunction "OUT_2") (pintype "passive"))
      (node (ref "U9") (pin "TAB") (pinfunction "OUT1_TAB") (pintype "passive"))
    )
    (net (code "2") (name "+3V3_A") (class "Default")
      (node (ref "C13") (pin "1") (pinfunction "1_1") (pintype "passive"))
      (node (ref "C14") (pin "+") (pinfunction "+_+") (pintype "passive"))
      (node (ref "C15") (pin "+") (pinfunction "+_+") (pintype "passive"))
      (node (ref "C3") (pin "1") (pinfunction "1_1") (pintype "passive"))
      (node (ref "C4") (pin "1") (pinfunction "1_1") (pintype "passive"))
      (node (ref "C43") (pin "1") (pinfunction "1_1") (pintype "passive"))
      (node (ref "C45") (pin "1") (pinfunction "1_1") (pintype "passive"))
      (node (ref "C46") (pin "1") (pinfunction "1_1") (pintype "passive"))
      (node (ref "C48") (pin "1") (pinfunction "1_1") (pintype "passive"))
      (node (ref "C53") (pin "+") (pinfunction "+_+") (pintype "passive"))
      (node (ref "C57") (pin "1") (pinfunction "1_1") (pintype "passive"))
      (node (ref "U1") (pin "14") (pinfunction "AVDD_14") (pintype "bidirectional"))
      (node (ref "U1") (pin "8") (pinfunction "HPVDD_8") (pintype "bidirectional"))
      (node (ref "U10") (pin "2") (pinfunction "OUT_2") (pintype "passive"))
      (node (ref "U10") (pin "TAB") (pinfunction "OUT1_TAB") (pintype "passive"))
      (node (ref "U11") (pin "13") (pinfunction "VDDA_13") (pintype "power_in"))
      (node (ref "U12") (pin "16") (pinfunction "VCC_16") (pintype "power_in"))
      (node (ref "U4") (pin "4") (pinfunction "V+_4") (pintype "power_in"))
      (node (ref "U5") (pin "4") (pinfunction "V+_4") (pintype "power_in"))
      (node (ref "U6") (pin "4") (pinfunction "V+_4") (pintype "power_in"))
      (node (ref "VR12") (pin "3") (pinfunction "3_3") (pintype "passive"))
      (node (ref "VR13") (pin "3") (pinfunction "3_3") (pintype "passive"))
      (node (ref "VR14") (pin "3") (pinfunction "3_3") (pintype "passive"))
      (node (ref "VR15") (pin "3") (pinfunction "3_3") (pintype "passive"))
      (node (ref "VR16") (pin "3") (pinfunction "3_3") (pintype "passive"))
      (node (ref "VR17") (pin "3") (pinfunction "3_3") (pintype "passive"))
      (node (ref "VR18") (pin "3") (pinfunction "3_3") (pintype "passive"))
      (node (ref "VR19") (pin "3") (pinfunction "3_3") (pintype "passive"))
      (node (ref "VR20") (pin "3") (pinfunction "3_3") (pintype "passive"))
    )
    (net (code "3") (name "+5V") (class "Default")
      (node (ref "C58") (pin "+") (pinfunction "+_+") (pintype "passive"))
      (node (ref "P2") (pin "5") (pinfunction "5_5") (pintype "passive"))
      (node (ref "R82") (pin "1") (pinfunction "1_1") (pintype "passive"))
      (node (ref "U10") (pin "3") (pinfunction "IN_3") (pintype "input"))
    )
    (net (code "4") (name "ADC_EN") (class "Default")
      (node (ref "U11") (pin "37") (pinfunction "PC6/I2S2_MCK_37") (pintype "bidirectional"))
      (node (ref "U12") (pin "6") (pinfunction "INH_6") (pintype "input"))
    )
    (net (code "5") (name "ADC_POT") (class "Default")
      (node (ref "U11") (pin "27") (pinfunction "PB1/ADC9/TIM3_CH4_27") (pintype "bidirectional"))
      (node (ref "U12") (pin "3") (pinfunction "X_3") (pintype "bidirectional"))
    )
    (net (code "6") (name "ADC_S0") (class "Default")
      (node (ref "U11") (pin "40") (pinfunction "PC9/I2S2_CKIN/I2S3_CKIN_40") (pintype "bidirectional"))
      (node (ref "U12") (pin "11") (pinfunction "A_11") (pintype "input"))
    )
    (net (code "7") (name "ADC_S1") (class "Default")
      (node (ref "U11") (pin "39") (pinfunction "PC8_39") (pintype "bidirectional"))
      (node (ref "U12") (pin "10") (pinfunction "B_10") (pintype "input"))
    )
    (net (code "8") (name "ADC_S2") (class "Default")
      (node (ref "U11") (pin "38") (pinfunction "PC7/I2S3_MCK_38") (pintype "bidirectional"))
      (node (ref "U12") (pin "9") (pinfunction "C_9") (pintype "input"))
    )
    (net (code "9") (name "AREF_-10") (class "Default")
      (node (ref "C59") (pin "1") (pinfunction "1_1") (pintype "passive"))
      (node (ref "R19") (pin "1") (pinfunction "1_1") (pintype "passive"))
      (node (ref "R21") (pin "1") (pinfunction "1_1") (pintype "passive"))
      (node (ref "R23") (pin "1") (pinfunction "1_1") (pintype "passive"))
      (node (ref "R25") (pin "1") (pinfunction "1_1") (pintype "passive"))
      (node (ref "R27") (pin "1") (pinfunction "1_1") (pintype "passive"))
      (node (ref "R42") (pin "1") (pinfunction "1_1") (pintype "passive"))
      (node (ref "R44") (pin "1") (pinfunction "1_1") (pintype "passive"))
      (node (ref "R46") (pin "1") (pinfunction "1_1") (pintype "passive"))
      (node (ref "R48") (pin "1") (pinfunction "1_1") (pintype "passive"))
      (node (ref "R83") (pin "2") (pinfunction "2_2") (pintype "passive"))
      (node (ref "U15") (pin "2") (pinfunction "A_2") (pintype "passive"))
    )
    (net (code "10") (name "BALANCE_CV") (class "Default")
      (node (ref "C38") (pin "2") (pinfunction "2_2") (pintype "passive"))
      (node (ref "R41") (pin "2") (pinfunction "2_2") (pintype "passive"))
      (node (ref "U11") (pin "20") (pinfunction "PA4/SPI1_NSS/SPI3_NSS/USART2_CK/I2S3_WS/ADC4/DAC1_20") (pintype "bidirectional"))
      (node (ref "U5") (pin "7") (pinfunction "OUT_7") (pintype "output"))
    )
    (net (code "11") (name "BALANCE_POT") (class "Default")
      (node (ref "U12") (pin "12") (pinfunction "X3_12") (pintype "bidirectional"))
      (node (ref "VR17") (pin "2") (pinfunction "2_2") (pintype "passive"))
    )
    (net (code "12") (name "BOOT_FLASH") (class "Default")
      (node (ref "R2") (pin "2") (pinfunction "2_2") (pintype "passive"))
      (node (ref "SJ2") (pin "1") (pinfunction "1_1") (pintype "passive"))
      (node (ref "U11") (pin "60") (pinfunction "BOOT0_60") (pintype "bidirectional"))
    )
    (net (code "13") (name "DENSITY_CV") (class "Default")
      (node (ref "C36") (pin "2") (pinfunction "2_2") (pintype "passive"))
      (node (ref "R39") (pin "2") (pinfunction "2_2") (pintype "passive"))
      (node (ref "U11") (pin "16") (pinfunction "PA2/USART2_TX/ADC2/TIM2_CH3_16") (pintype "bidirectional"))
      (node (ref "U4") (pin "14") (pinfunction "OUT_14") (pintype "output"))
    )
    (net (code "14") (name "DENSITY_POT") (class "Default")
      (node (ref "U12") (pin "4") (pinfunction "X7_4") (pintype "bidirectional"))
      (node (ref "VR19") (pin "2") (pinfunction "2_2") (pintype "passive"))
    )
    (net (code "15") (name "FEEDBACK_CV") (class "Default")
      (node (ref "C40") (pin "2") (pinfunction "2_2") (pintype "passive"))
      (node (ref "R59") (pin "2") (pinfunction "2_2") (pintype "passive"))
      (node (ref "U11") (pin "22") (pinfunction "PA6/SPI1_MISO/ADC6/TIM3_CH1_22") (pintype "bidirectional"))
      (node (ref "U6") (pin "7") (pinfunction "OUT_7") (pintype "output"))
    )
    (net (code "16") (name "FEEDBACK_POT") (class "Default")
      (node (ref "U12") (pin "14") (pinfunction "X1_14") (pintype "bidirectional"))
      (node (ref "VR16") (pin "2") (pinfunction "2_2") (pintype "passive"))
    )
    (net (code "17") (name "GATE_CAPT") (class "Default")
      (node (ref "Q1") (pin "C") (pinfunction "C_C") (pintype "passive"))
      (node (ref "R65") (pin "1") (pinfunction "1_1") (pintype "passive"))
      (node (ref "U11") (pin "56") (pinfunction "PB4/NJTRST/SPI3_MISO/SPI1_MISO_56") (pintype "bidirectional"))
    )
    (net (code "18") (name "GATE_FREEZE") (class "Default")
      (node (ref "Q2") (pin "C") (pinfunction "C_C") (pintype "passive"))
      (node (ref "R66") (pin "1") (pinfunction "1_1") (pintype "passive"))
      (node (ref "U11") (pin "24") (pinfunction "PC4/ADC14_24") (pintype "bidirectional"))
    )
    (net (code "19") (name "GND") (class "Default")
      (node (ref "C1") (pin "2") (pinfunction "2_2") (pintype "passive"))
      (node (ref "C10") (pin "2") (pinfunction "2_2") (pintype "passive"))
      (node (ref "C11") (pin "-") (pinfunction "-_-") (pintype "passive"))
      (node (ref "C12") (pin "2") (pinfunction "2_2") (pintype "passive"))
      (node (ref "C13") (pin "2") (pinfunction "2_2") (pintype "passive"))
      (node (ref "C14") (pin "-") (pinfunction "-_-") (pintype "passive"))
      (node (ref "C15") (pin "-") (pinfunction "-_-") (pintype "passive"))
      (node (ref "C16") (pin "1") (pinfunction "1_1") (pintype "passive"))
      (node (ref "C17") (pin "1") (pinfunction "1_1") (pintype "passive"))
      (node (ref "C18") (pin "1") (pinfunction "1_1") (pintype "passive"))
      (node (ref "C19") (pin "1") (pinfunction "1_1") (pintype "passive"))
      (node (ref "C2") (pin "2") (pinfunction "2_2") (pintype "passive"))
      (node (ref "C20") (pin "2") (pinfunction "2_2") (pintype "passive"))
      (node (ref "C21") (pin "-") (pinfunction "-_-") (pintype "passive"))
      (node (ref "C22") (pin "2") (pinfunction "2_2") (pintype "passive"))
      (node (ref "C23") (pin "2") (pinfunction "2_2") (pintype "passive"))
      (node (ref "C3") (pin "2") (pinfunction "2_2") (pintype "passive"))
      (node (ref "C30") (pin "2") (pinfunction "2_2") (pintype "passive"))
      (node (ref "C31") (pin "1") (pinfunction "1_1") (pintype "passive"))
      (node (ref "C32") (pin "2") (pinfunction "2_2") (pintype "passive"))
      (node (ref "C33") (pin "1") (pinfunction "1_1") (pintype "passive"))
      (node (ref "C4") (pin "2") (pinfunction "2_2") (pintype "passive"))
      (node (ref "C43") (pin "2") (pinfunction "2_2") (pintype "passive"))
      (node (ref "C45") (pin "2") (pinfunction "2_2") (pintype "passive"))
      (node (ref "C46") (pin "2") (pinfunction "2_2") (pintype "passive"))
      (node (ref "C48") (pin "2") (pinfunction "2_2") (pintype "passive"))
      (node (ref "C49") (pin "2") (pinfunction "2_2") (pintype "passive"))
      (node (ref "C5") (pin "2") (pinfunction "2_2") (pintype "passive"))
      (node (ref "C50") (pin "2") (pinfunction "2_2") (pintype "passive"))
      (node (ref "C51") (pin "-") (pinfunction "-_-") (pintype "passive"))
      (node (ref "C52") (pin "-") (pinfunction "-_-") (pintype "passive"))
      (node (ref "C53") (pin "-") (pinfunction "-_-") (pintype "passive"))
      (node (ref "C54") (pin "-") (pinfunction "-_-") (pintype "passive"))
      (node (ref "C55") (pin "+") (pinfunction "+_+") (pintype "passive"))
      (node (ref "C56") (pin "2") (pinfunction "2_2") (pintype "passive"))
      (node (ref "C57") (pin "2") (pinfunction "2_2") (pintype "passive"))
      (node (ref "C58") (pin "-") (pinfunction "-_-") (pintype "passive"))
      (node (ref "C59") (pin "2") (pinfunction "2_2") (pintype "passive"))
      (node (ref "C6") (pin "2") (pinfunction "2_2") (pintype "passive"))
      (node (ref "C60") (pin "2") (pinfunction "2_2") (pintype "passive"))
      (node (ref "C61") (pin "1") (pinfunction "1_1") (pintype "passive"))
      (node (ref "C62") (pin "1") (pinfunction "1_1") (pintype "passive"))
      (node (ref "C63") (pin "2") (pinfunction "2_2") (pintype "passive"))
      (node (ref "C7") (pin "2") (pinfunction "2_2") (pintype "passive"))
      (node (ref "C8") (pin "2") (pinfunction "2_2") (pintype "passive"))
      (node (ref "C9") (pin "2") (pinfunction "2_2") (pintype "passive"))
      (node (ref "J1") (pin "G") (pinfunction "1_G") (pintype "passive"))
      (node (ref "J2") (pin "G") (pinfunction "1_G") (pintype "passive"))
      (node (ref "J3") (pin "G") (pinfunction "1_G") (pintype "passive"))
      (node (ref "J4") (pin "G") (pinfunction "1_G") (pintype "passive"))
      (node (ref "LED1") (pin "K") (pinfunction "C_K") (pintype "passive"))
      (node (ref "LED10") (pin "K") (pinfunction "C_K") (pintype "passive"))
      (node (ref "LED11") (pin "K") (pinfunction "C_K") (pintype "passive"))
      (node (ref "LED12") (pin "K") (pinfunction "C_K") (pintype "passive"))
      (node (ref "LED13") (pin "K") (pinfunction "C_K") (pintype "passive"))
      (node (ref "LED14") (pin "K") (pinfunction "C_K") (pintype "passive"))
      (node (ref "LED15") (pin "K") (pinfunction "C_K") (pintype "passive"))
      (node (ref "LED2") (pin "K") (pinfunction "C_K") (pintype "passive"))
      (node (ref "LED3") (pin "K") (pinfunction "C_K") (pintype "passive"))
      (node (ref "LED4") (pin "K") (pinfunction "C_K") (pintype "passive"))
      (node (ref "LED5") (pin "K") (pinfunction "C_K") (pintype "passive"))
      (node (ref "LED6") (pin "K") (pinfunction "C_K") (pintype "passive"))
      (node (ref "LED7") (pin "K") (pinfunction "C_K") (pintype "passive"))
      (node (ref "LED8") (pin "K") (pinfunction "C_K") (pintype "passive"))
      (node (ref "LED9") (pin "K") (pinfunction "C_K") (pintype "passive"))
      (node (ref "P1") (pin "3") (pinfunction "3_3") (pintype "passive"))
      (node (ref "P1") (pin "5") (pinfunction "5_5") (pintype "passive"))
      (node (ref "P1") (pin "9") (pinfunction "9_9") (pintype "passive"))
      (node (ref "P2") (pin "1") (pinfunction "1_1") (pintype "passive"))
      (node (ref "Q1") (pin "E") (pinfunction "E_E") (pintype "passive"))
      (node (ref "Q2") (pin "E") (pinfunction "E_E") (pintype "passive"))
      (node (ref "R11") (pin "1") (pinfunction "1_1") (pintype "passive"))
      (node (ref "R12") (pin "1") (pinfunction "1_1") (pintype "passive"))
      (node (ref "R13") (pin "2") (pinfunction "2_2") (pintype "passive"))
      (node (ref "R14") (pin "2") (pinfunction "2_2") (pintype "passive"))
      (node (ref "R2") (pin "1") (pinfunction "1_1") (pintype "passive"))
      (node (ref "S1") (pin "1") (pinfunction "1_1") (pintype "passive"))
      (node (ref "S1") (pin "2") (pinfunction "2_2") (pintype "passive"))
      (node (ref "S2") (pin "1") (pinfunction "1_1") (pintype "passive"))
      (node (ref "S2") (pin "2") (pinfunction "2_2") (pintype "passive"))
      (node (ref "S3") (pin "1") (pinfunction "1_1") (pintype "passive"))
      (node (ref "S3") (pin "2") (pinfunction "2_2") (pintype "passive"))
      (node (ref "S4") (pin "1") (pinfunction "2_1") (pintype "passive"))
      (node (ref "S4") (pin "4") (pinfunction "L2_4") (pintype "passive"))
      (node (ref "SJ1") (pin "1") (pinfunction "1_1") (pintype "passive"))
      (node (ref "U1") (pin "11") (pinfunction "HPGND_11") (pintype "bidirectional"))
      (node (ref "U1") (pin "15") (pinfunction "AGND_15") (pintype "bidirectional"))
      (node (ref "U1") (pin "21") (pinfunction "MODE_21") (pintype "bidirectional"))
      (node (ref "U1") (pin "22") (pinfunction "CSB_22") (pintype "bidirectional"))
      (node (ref "U1") (pin "28") (pinfunction "DGND_28") (pintype "bidirectional"))
      (node (ref "U10") (pin "1") (pinfunction "GND_1") (pintype "input"))
      (node (ref "U11") (pin "12") (pinfunction "VSSA_12") (pintype "power_in"))
      (node (ref "U11") (pin "18") (pinfunction "VSS_4_18") (pintype "power_in"))
      (node (ref "U11") (pin "26") (pinfunction "PB0/ADC8/TIM3_CH3_26") (pintype "bidirectional"))
      (node (ref "U11") (pin "28") (pinfunction "PB2/BOOT1_28") (pintype "bidirectional"))
      (node (ref "U11") (pin "63") (pinfunction "VSS_3_63") (pintype "power_in"))
      (node (ref "U12") (pin "7") (pinfunction "VEE_7") (pintype "power_in"))
      (node (ref "U12") (pin "8") (pinfunction "GND_8") (pintype "power_in"))
      (node (ref "U13") (pin "13") (pinfunction "G_13") (pintype "input"))
      (node (ref "U13") (pin "8") (pinfunction "GND_8") (pintype "power_in"))
      (node (ref "U14") (pin "13") (pinfunction "G_13") (pintype "input"))
      (node (ref "U14") (pin "8") (pinfunction "GND_8") (pintype "power_in"))
      (node (ref "U15") (pin "1") (pinfunction "C_1") (pintype "passive"))
      (node (ref "U2") (pin "3") (pinfunction "+IN_3") (pintype "input"))
      (node (ref "U2") (pin "5") (pinfunction "+IN_5") (pintype "input"))
      (node (ref "U4") (pin "10") (pinfunction "+IN_10") (pintype "input"))
      (node (ref "U4") (pin "11") (pinfunction "V-_11") (pintype "power_in"))
      (node (ref "U4") (pin "12") (pinfunction "+IN_12") (pintype "input"))
      (node (ref "U4") (pin "3") (pinfunction "+IN_3") (pintype "input"))
      (node (ref "U4") (pin "5") (pinfunction "+IN_5") (pintype "input"))
      (node (ref "U5") (pin "11") (pinfunction "V-_11") (pintype "power_in"))
      (node (ref "U5") (pin "13") (pinfunction "-IN_13") (pintype "input"))
      (node (ref "U5") (pin "2") (pinfunction "-IN_2") (pintype "input"))
      (node (ref "U5") (pin "5") (pinfunction "+IN_5") (pintype "input"))
      (node (ref "U5") (pin "9") (pinfunction "-IN_9") (pintype "input"))
      (node (ref "U6") (pin "10") (pinfunction "+IN_10") (pintype "input"))
      (node (ref "U6") (pin "11") (pinfunction "V-_11") (pintype "power_in"))
      (node (ref "U6") (pin "12") (pinfunction "+IN_12") (pintype "input"))
      (node (ref "U6") (pin "3") (pinfunction "+IN_3") (pintype "input"))
      (node (ref "U6") (pin "5") (pinfunction "+IN_5") (pintype "input"))
      (node (ref "U7") (pin "10") (pinfunction "+IN_10") (pintype "input"))
      (node (ref "U7") (pin "12") (pinfunction "+IN_12") (pintype "input"))
      (node (ref "U7") (pin "3") (pinfunction "+IN_3") (pintype "input"))
      (node (ref "U7") (pin "5") (pinfunction "+IN_5") (pintype "input"))
      (node (ref "U8") (pin "10") (pinfunction "+IN_10") (pintype "input"))
      (node (ref "U8") (pin "12") (pinfunction "+IN_12") (pintype "input"))
      (node (ref "U8") (pin "3") (pinfunction "+IN_3") (pintype "input"))
      (node (ref "U8") (pin "5") (pinfunction "+IN_5") (pintype "input"))
      (node (ref "U9") (pin "1") (pinfunction "GND_1") (pintype "input"))
      (node (ref "VR12") (pin "1") (pinfunction "1_1") (pintype "passive"))
      (node (ref "VR13") (pin "1") (pinfunction "1_1") (pintype "passive"))
      (node (ref "VR14") (pin "1") (pinfunction "1_1") (pintype "passive"))
      (node (ref "VR15") (pin "1") (pinfunction "1_1") (pintype "passive"))
      (node (ref "VR16") (pin "1") (pinfunction "1_1") (pintype "passive"))
      (node (ref "VR17") (pin "1") (pinfunction "1_1") (pintype "passive"))
      (node (ref "VR18") (pin "1") (pinfunction "1_1") (pintype "passive"))
      (node (ref "VR19") (pin "1") (pinfunction "1_1") (pintype "passive"))
      (node (ref "VR2") (pin "1R1") (pinfunction "1_1R1") (pintype "passive"))
      (node (ref "VR2") (pin "1R2") (pinfunction "1_1R2") (pintype "passive"))
      (node (ref "VR20") (pin "1") (pinfunction "1_1") (pintype "passive"))
      (node (ref "VR3") (pin "1") (pinfunction "1_1") (pintype "passive"))
    )
    (net (code "20") (name "GRAIN_CV") (class "Default")
      (node (ref "C42") (pin "2") (pinfunction "2_2") (pintype "passive"))
      (node (ref "R61") (pin "2") (pinfunction "2_2") (pintype "passive"))
      (node (ref "U11") (pin "9") (pinfunction "PC1/ADC11_9") (pintype "bidirectional"))
      (node (ref "U6") (pin "8") (pinfunction "OUT_8") (pintype "output"))
    )
    (net (code "21") (name "GRAIN_POT") (class "Default")
      (node (ref "U11") (pin "8") (pinfunction "PC0/ADC10_8") (pintype "bidirectional"))
      (node (ref "VR20") (pin "2") (pinfunction "2_2") (pintype "passive"))
    )
    (net (code "22") (name "I2C_SCL") (class "Default")
      (node (ref "R3") (pin "1") (pinfunction "1_1") (pintype "passive"))
      (node (ref "U1") (pin "24") (pinfunction "SCLK_24") (pintype "bidirectional"))
      (node (ref "U11") (pin "29") (pinfunction "PB10/SPI2_SCK/I2S_SCK/I2C2_SCL/USART3_TX_29") (pintype "bidirectional"))
    )
    (net (code "23") (name "I2C_SDA") (class "Default")
      (node (ref "R4") (pin "1") (pinfunction "1_1") (pintype "passive"))
      (node (ref "U1") (pin "23") (pinfunction "SDIN_23") (pintype "bidirectional"))
      (node (ref "U11") (pin "30") (pinfunction "PB11/I2C2_SDA/USART3_RX_30") (pintype "bidirectional"))
    )
    (net (code "24") (name "I2S_LRCK") (class "Default")
      (node (ref "U1") (pin "5") (pinfunction "DACLRC_5") (pintype "bidirectional"))
      (node (ref "U1") (pin "7") (pinfunction "ADCLRC_7") (pintype "bidirectional"))
      (node (ref "U11") (pin "33") (pinfunction "PB12/SPI2_NSS/I2S2_WS/I2C2_SMBA/USART3_CK/TIM1_BKIN_33") (pintype "bidirectional"))
    )
    (net (code "25") (name "I2S_SCK") (class "Default")
      (node (ref "U1") (pin "3") (pinfunction "BCLK_3") (pintype "bidirectional"))
      (node (ref "U11") (pin "34") (pinfunction "PB13/SPI2_SCK/I2S2_SCK/USART3_CTS/TIM1_CH1N_34") (pintype "bidirectional"))
    )
    (net (code "26") (name "I2S_SIN") (class "Default")
      (node (ref "U1") (pin "6") (pinfunction "ADCDAT_6") (pintype "bidirectional"))
      (node (ref "U11") (pin "35") (pinfunction "PB14/SPI2_MISO/USART3_RTS/TIM1_CH2N_35") (pintype "bidirectional"))
    )
    (net (code "27") (name "I2S_SOUT") (class "Default")
      (node (ref "U1") (pin "4") (pinfunction "DACDAT_4") (pintype "bidirectional"))
      (node (ref "U11") (pin "36") (pinfunction "PB15/SPI2_MOSI/I2S2_SD/TIM1_CH3N_36") (pintype "bidirectional"))
    )
    (net (code "28") (name "JTCK") (class "Default")
      (node (ref "P1") (pin "4") (pinfunction "4_4") (pintype "passive"))
      (node (ref "U11") (pin "49") (pinfunction "PA14/JTCK-SWCLK_49") (pintype "bidirectional"))
    )
    (net (code "29") (name "JTDI") (class "Default")
      (node (ref "P1") (pin "8") (pinfunction "8_8") (pintype "passive"))
      (node (ref "U11") (pin "50") (pinfunction "PA15/JTDI/SPI3_NSS/I2S3_WS_50") (pintype "bidirectional"))
    )
    (net (code "30") (name "JTDO") (class "Default")
      (node (ref "P1") (pin "6") (pinfunction "6_6") (pintype "passive"))
      (node (ref "U11") (pin "55") (pinfunction "PB3/JTDO/SPI3_SCK/I2S3_SCK_55") (pintype "bidirectional"))
    )
    (net (code "31") (name "JTMS") (class "Default")
      (node (ref "P1") (pin "2") (pinfunction "2_2") (pintype "passive"))
      (node (ref "U11") (pin "46") (pinfunction "PA13/JTMS-SWDAT_46") (pintype "bidirectional"))
    )
    (net (code "32") (name "LED_DATA") (class "Default")
      (node (ref "U11") (pin "53") (pinfunction "PC12/UART5_TX/I2S3_SD/USART3_CK_53") (pintype "bidirectional"))
      (node (ref "U13") (pin "14") (pinfunction "SER_14") (pintype "input"))
    )
    (net (code "33") (name "LED_EN") (class "Default")
      (node (ref "U11") (pin "52") (pinfunction "PC11/UART4_RX/SPI3_MISO/USART3_RX_52") (pintype "bidirectional"))
      (node (ref "U13") (pin "12") (pinfunction "RCK_12") (pintype "input"))
      (node (ref "U14") (pin "12") (pinfunction "RCK_12") (pintype "input"))
    )
    (net (code "34") (name "LED_FREEZE") (class "Default")
      (node (ref "R64") (pin "1") (pinfunction "1_1") (pintype "passive"))
      (node (ref "U11") (pin "11") (pinfunction "PC3/SPI2_MOSI/I2S2_SD/ADC13_11") (pintype "bidirectional"))
    )
    (net (code "35") (name "LED_SCK") (class "Default")
      (node (ref "U11") (pin "51") (pinfunction "PC10/SPI3_SCK/I2S3_SCK/UART4_TX_51") (pintype "bidirectional"))
      (node (ref "U13") (pin "11") (pinfunction "SCK_11") (pintype "input"))
      (node (ref "U14") (pin "11") (pinfunction "SCK_11") (pintype "input"))
    )
    (net (code "36") (name "LIN") (class "Default")
      (node (ref "C25") (pin "+") (pinfunction "+_+") (pintype "passive"))
      (node (ref "U1") (pin "20") (pinfunction "LLINEIN_20") (pintype "bidirectional"))
    )
    (net (code "37") (name "LOUT") (class "Default")
      (node (ref "C27") (pin "+") (pinfunction "+_+") (pintype "passive"))
      (node (ref "U1") (pin "12") (pinfunction "LOUT_12") (pintype "bidirectional"))
    )
    (net (code "38") (name "N$32") (class "Default")
      (node (ref "C29") (pin "1") (pinfunction "1_1") (pintype "passive"))
      (node (ref "R14") (pin "1") (pinfunction "1_1") (pintype "passive"))
      (node (ref "R15") (pin "2") (pinfunction "2_2") (pintype "passive"))
      (node (ref "U3") (pin "2") (pinfunction "-IN_2") (pintype "input"))
    )
    (net (code "39") (name "N$61") (class "Default")
      (node (ref "U3") (pin "3") (pinfunction "+IN_3") (pintype "input"))
      (node (ref "VR2") (pin "2R2") (pinfunction "2_2R2") (pintype "passive"))
    )
    (net (code "40") (name "Net-(C22-Pad1)") (class "Default")
      (node (ref "C22") (pin "1") (pinfunction "1_1") (pintype "passive"))
      (node (ref "C24") (pin "-") (pinfunction "-_-") (pintype "passive"))
      (node (ref "R11") (pin "2") (pinfunction "2_2") (pintype "passive"))
      (node (ref "R9") (pin "1") (pinfunction "1_1") (pintype "passive"))
    )
    (net (code "41") (name "Net-(C23-Pad1)") (class "Default")
      (node (ref "C23") (pin "1") (pinfunction "1_1") (pintype "passive"))
      (node (ref "C25") (pin "-") (pinfunction "-_-") (pintype "passive"))
      (node (ref "R10") (pin "1") (pinfunction "1_1") (pintype "passive"))
      (node (ref "R12") (pin "2") (pinfunction "2_2") (pintype "passive"))
    )
    (net (code "42") (name "Net-(J1-2)") (class "Default")
      (node (ref "J1") (pin "C") (pinfunction "2_C") (pintype "passive"))
      (node (ref "J2") (pin "S") (pinfunction "2_S") (pintype "passive"))
      (node (ref "R6") (pin "2") (pinfunction "2_2") (pintype "passive"))
    )
    (net (code "43") (name "Net-(J1-3)") (class "Default")
      (node (ref "J1") (pin "S") (pinfunction "3_S") (pintype "passive"))
      (node (ref "R5") (pin "2") (pinfunction "2_2") (pintype "passive"))
    )
    (net (code "44") (name "Net-(J3-2)") (class "Default")
      (node (ref "J3") (pin "S") (pinfunction "2_S") (pintype "passive"))
      (node (ref "R17") (pin "1") (pinfunction "1_1") (pintype "passive"))
    )
    (net (code "45") (name "Net-(J4-2)") (class "Default")
      (node (ref "J4") (pin "S") (pinfunction "2_S") (pintype "passive"))
      (node (ref "R18") (pin "1") (pinfunction "1_1") (pintype "passive"))
    )
    (net (code "46") (name "Net-(J5-Pad1)") (class "Default")
      (node (ref "J5") (pin "1") (pinfunction "1_1") (pintype "output"))
      (node (ref "R20") (pin "1") (pinfunction "1_1") (pintype "passive"))
    )
    (net (code "47") (name "Net-(J6-Pad1)") (class "Default")
      (node (ref "J6") (pin "1") (pinfunction "1_1") (pintype "output"))
      (node (ref "VR3") (pin "3") (pinfunction "3_3") (pintype "passive"))
    )
    (net (code "48") (name "Net-(J7-Pad1)") (class "Default")
      (node (ref "J7") (pin "1") (pinfunction "1_1") (pintype "output"))
      (node (ref "R24") (pin "1") (pinfunction "1_1") (pintype "passive"))
    )
    (net (code "49") (name "Net-(J8-Pad1)") (class "Default")
      (node (ref "J8") (pin "1") (pinfunction "1_1") (pintype "output"))
      (node (ref "R26") (pin "1") (pinfunction "1_1") (pintype "passive"))
    )
    (net (code "50") (name "Net-(J9-Pad1)") (class "Default")
      (node (ref "J9") (pin "1") (pinfunction "1_1") (pintype "output"))
      (node (ref "R28") (pin "1") (pinfunction "1_1") (pintype "passive"))
    )
    (net (code "51") (name "Net-(J10-Pad1)") (class "Default")
      (node (ref "J10") (pin "1") (pinfunction "1_1") (pintype "output"))
      (node (ref "R43") (pin "1") (pinfunction "1_1") (pintype "passive"))
    )
    (net (code "52") (name "Net-(J11-Pad1)") (class "Default")
      (node (ref "J11") (pin "1") (pinfunction "1_1") (pintype "output"))
      (node (ref "R45") (pin "1") (pinfunction "1_1") (pintype "passive"))
    )
    (net (code "53") (name "Net-(J12-Pad1)") (class "Default")
      (node (ref "J12") (pin "1") (pinfunction "1_1") (pintype "output"))
      (node (ref "R47") (pin "1") (pinfunction "1_1") (pintype "passive"))
    )
    (net (code "54") (name "Net-(J13-Pad1)") (class "Default")
      (node (ref "J13") (pin "1") (pinfunction "1_1") (pintype "output"))
      (node (ref "R49") (pin "1") (pinfunction "1_1") (pintype "passive"))
    )
    (net (code "55") (name "Net-(J14-Pad1)") (class "Default")
      (node (ref "J14") (pin "1") (pinfunction "1_1") (pintype "output"))
      (node (ref "R62") (pin "1") (pinfunction "1_1") (pintype "passive"))
    )
    (net (code "56") (name "Net-(J15-Pad1)") (class "Default")
      (node (ref "J15") (pin "1") (pinfunction "1_1") (pintype "output"))
      (node (ref "R63") (pin "1") (pinfunction "1_1") (pintype "passive"))
    )
    (net (code "57") (name "Net-(LED1-PadA)") (class "Default")
      (node (ref "LED1") (pin "A") (pinfunction "A_A") (pintype "passive"))
      (node (ref "R67") (pin "1") (pinfunction "1_1") (pintype "passive"))
    )
    (net (code "58") (name "Net-(LED2-PadA)") (class "Default")
      (node (ref "LED2") (pin "A") (pinfunction "A_A") (pintype "passive"))
      (node (ref "R68") (pin "1") (pinfunction "1_1") (pintype "passive"))
    )
    (net (code "59") (name "Net-(LED3-PadA)") (class "Default")
      (node (ref "LED3") (pin "A") (pinfunction "A_A") (pintype "passive"))
      (node (ref "R69") (pin "1") (pinfunction "1_1") (pintype "passive"))
    )
    (net (code "60") (name "Net-(LED4-PadA)") (class "Default")
      (node (ref "LED4") (pin "A") (pinfunction "A_A") (pintype "passive"))
      (node (ref "R70") (pin "1") (pinfunction "1_1") (pintype "passive"))
    )
    (net (code "61") (name "Net-(LED5-PadA)") (class "Default")
      (node (ref "LED5") (pin "A") (pinfunction "A_A") (pintype "passive"))
      (node (ref "R71") (pin "1") (pinfunction "1_1") (pintype "passive"))
    )
    (net (code "62") (name "Net-(LED6-PadA)") (class "Default")
      (node (ref "LED6") (pin "A") (pinfunction "A_A") (pintype "passive"))
      (node (ref "R72") (pin "1") (pinfunction "1_1") (pintype "passive"))
    )
    (net (code "63") (name "Net-(LED7-PadA)") (class "Default")
      (node (ref "LED7") (pin "A") (pinfunction "A_A") (pintype "passive"))
      (node (ref "R73") (pin "1") (pinfunction "1_1") (pintype "passive"))
    )
    (net (code "64") (name "Net-(LED8-PadA)") (class "Default")
      (node (ref "LED8") (pin "A") (pinfunction "A_A") (pintype "passive"))
      (node (ref "R74") (pin "1") (pinfunction "1_1") (pintype "passive"))
    )
    (net (code "65") (name "Net-(LED9-PadA)") (class "Default")
      (node (ref "LED9") (pin "A") (pinfunction "A_A") (pintype "passive"))
      (node (ref "R75") (pin "1") (pinfunction "1_1") (pintype "passive"))
    )
    (net (code "66") (name "Net-(LED10-PadA)") (class "Default")
      (node (ref "LED10") (pin "A") (pinfunction "A_A") (pintype "passive"))
      (node (ref "R76") (pin "1") (pinfunction "1_1") (pintype "passive"))
    )
    (net (code "67") (name "Net-(LED11-PadA)") (class "Default")
      (node (ref "LED11") (pin "A") (pinfunction "A_A") (pintype "passive"))
      (node (ref "R77") (pin "1") (pinfunction "1_1") (pintype "passive"))
    )
    (net (code "68") (name "Net-(LED12-PadA)") (class "Default")
      (node (ref "LED12") (pin "A") (pinfunction "A_A") (pintype "passive"))
      (node (ref "R78") (pin "1") (pinfunction "1_1") (pintype "passive"))
    )
    (net (code "69") (name "Net-(LED13-PadA)") (class "Default")
      (node (ref "LED13") (pin "A") (pinfunction "A_A") (pintype "passive"))
      (node (ref "R79") (pin "1") (pinfunction "1_1") (pintype "passive"))
    )
    (net (code "70") (name "Net-(LED14-PadA)") (class "Default")
      (node (ref "LED14") (pin "A") (pinfunction "A_A") (pintype "passive"))
      (node (ref "R80") (pin "1") (pinfunction "1_1") (pintype "passive"))
    )
    (net (code "71") (name "Net-(LED15-PadA)") (class "Default")
      (node (ref "LED15") (pin "A") (pinfunction "A_A") (pintype "passive"))
      (node (ref "R81") (pin "1") (pinfunction "1_1") (pintype "passive"))
    )
    (net (code "72") (name "Net-(Q1-PadB)") (class "Default")
      (node (ref "Q1") (pin "B") (pinfunction "B_B") (pintype "passive"))
      (node (ref "R62") (pin "2") (pinfunction "2_2") (pintype "passive"))
    )
    (net (code "73") (name "Net-(Q2-PadB)") (class "Default")
      (node (ref "Q2") (pin "B") (pinfunction "B_B") (pintype "passive"))
      (node (ref "R63") (pin "2") (pinfunction "2_2") (pintype "passive"))
    )
    (net (code "74") (name "Net-(R20-Pad2)") (class "Default")
      (node (ref "R20") (pin "2") (pinfunction "2_2") (pintype "passive"))
      (node (ref "VR4") (pin "2") (pinfunction "2_2") (pintype "passive"))
    )
    (net (code "75") (name "Net-(R22-Pad1)") (class "Default")
      (node (ref "R22") (pin "1") (pinfunction "1_1") (pintype "passive"))
      (node (ref "VR3") (pin "2") (pinfunction "2_2") (pintype "passive"))
    )
    (net (code "76") (name "Net-(R24-Pad2)") (class "Default")
      (node (ref "R24") (pin "2") (pinfunction "2_2") (pintype "passive"))
      (node (ref "VR5") (pin "2") (pinfunction "2_2") (pintype "passive"))
    )
    (net (code "77") (name "Net-(R26-Pad2)") (class "Default")
      (node (ref "R26") (pin "2") (pinfunction "2_2") (pintype "passive"))
      (node (ref "VR6") (pin "2") (pinfunction "2_2") (pintype "passive"))
    )
    (net (code "78") (name "Net-(R28-Pad2)") (class "Default")
      (node (ref "R28") (pin "2") (pinfunction "2_2") (pintype "passive"))
      (node (ref "VR7") (pin "2") (pinfunction "2_2") (pintype "passive"))
    )
    (net (code "79") (name "Net-(R43-Pad2)") (class "Default")
      (node (ref "R43") (pin "2") (pinfunction "2_2") (pintype "passive"))
      (node (ref "VR8") (pin "2") (pinfunction "2_2") (pintype "passive"))
    )
    (net (code "80") (name "Net-(R45-Pad2)") (class "Default")
      (node (ref "R45") (pin "2") (pinfunction "2_2") (pintype "passive"))
      (node (ref "VR9") (pin "2") (pinfunction "2_2") (pintype "passive"))
    )
    (net (code "81") (name "Net-(R47-Pad2)") (class "Default")
      (node (ref "R47") (pin "2") (pinfunction "2_2") (pintype "passive"))
      (node (ref "VR10") (pin "2") (pinfunction "2_2") (pintype "passive"))
    )
    (net (code "82") (name "Net-(R49-Pad2)") (class "Default")
      (node (ref "R49") (pin "2") (pinfunction "2_2") (pintype "passive"))
      (node (ref "VR11") (pin "2") (pinfunction "2_2") (pintype "passive"))
    )
    (net (code "83") (name "Net-(S4B-L1)") (class "Default")
      (node (ref "R64") (pin "2") (pinfunction "2_2") (pintype "passive"))
      (node (ref "S4") (pin "3") (pinfunction "L1_3") (pintype "passive"))
    )
    (net (code "84") (name "Net-(U1-VMID)") (class "Default")
      (node (ref "C20") (pin "1") (pinfunction "1_1") (pintype "passive"))
      (node (ref "C21") (pin "+") (pinfunction "+_+") (pintype "passive"))
      (node (ref "U1") (pin "16") (pinfunction "VMID_16") (pintype "bidirectional"))
    )
    (net (code "85") (name "Net-(U1-XTI{slash}MCLK)") (class "Default")
      (node (ref "C18") (pin "2") (pinfunction "2_2") (pintype "passive"))
      (node (ref "U1") (pin "25") (pinfunction "XTI/MCLK_25") (pintype "bidirectional"))
      (node (ref "Y2") (pin "2") (pinfunction "2_2") (pintype "passive"))
    )
    (net (code "86") (name "Net-(U1-XTO)") (class "Default")
      (node (ref "C19") (pin "2") (pinfunction "2_2") (pintype "passive"))
      (node (ref "U1") (pin "26") (pinfunction "XTO_26") (pintype "bidirectional"))
      (node (ref "Y2") (pin "1") (pinfunction "1_1") (pintype "passive"))
    )
    (net (code "87") (name "Net-(U2A--IN)") (class "Default")
      (node (ref "R6") (pin "1") (pinfunction "1_1") (pintype "passive"))
      (node (ref "R8") (pin "2") (pinfunction "2_2") (pintype "passive"))
      (node (ref "U2") (pin "2") (pinfunction "-IN_2") (pintype "input"))
    )
    (net (code "88") (name "Net-(U2A-OUT)") (class "Default")
      (node (ref "R10") (pin "2") (pinfunction "2_2") (pintype "passive"))
      (node (ref "U2") (pin "1") (pinfunction "OUT_1") (pintype "output"))
      (node (ref "VR1") (pin "2R2") (pinfunction "2_2R2") (pintype "passive"))
      (node (ref "VR1") (pin "3R2") (pinfunction "3_3R2") (pintype "passive"))
    )
    (net (code "89") (name "Net-(U2B--IN)") (class "Default")
      (node (ref "R5") (pin "1") (pinfunction "1_1") (pintype "passive"))
      (node (ref "R7") (pin "2") (pinfunction "2_2") (pintype "passive"))
      (node (ref "U2") (pin "6") (pinfunction "-IN_6") (pintype "input"))
    )
    (net (code "90") (name "Net-(U2B-OUT)") (class "Default")
      (node (ref "R9") (pin "2") (pinfunction "2_2") (pintype "passive"))
      (node (ref "U2") (pin "7") (pinfunction "OUT_7") (pintype "output"))
      (node (ref "VR1") (pin "2R1") (pinfunction "2_2R1") (pintype "passive"))
      (node (ref "VR1") (pin "3R1") (pinfunction "3_3R1") (pintype "passive"))
    )
    (net (code "91") (name "Net-(U3A-OUT)") (class "Default")
      (node (ref "C29") (pin "2") (pinfunction "2_2") (pintype "passive"))
      (node (ref "R15") (pin "1") (pinfunction "1_1") (pintype "passive"))
      (node (ref "R18") (pin "2") (pinfunction "2_2") (pintype "passive"))
      (node (ref "U3") (pin "1") (pinfunction "OUT_1") (pintype "output"))
    )
    (net (code "92") (name "Net-(U3B-+IN)") (class "Default")
      (node (ref "U3") (pin "5") (pinfunction "+IN_5") (pintype "input"))
      (node (ref "VR2") (pin "2R1") (pinfunction "2_2R1") (pintype "passive"))
    )
    (net (code "93") (name "Net-(U3B--IN)") (class "Default")
      (node (ref "C28") (pin "1") (pinfunction "1_1") (pintype "passive"))
      (node (ref "R13") (pin "1") (pinfunction "1_1") (pintype "passive"))
      (node (ref "R16") (pin "2") (pinfunction "2_2") (pintype "passive"))
      (node (ref "U3") (pin "6") (pinfunction "-IN_6") (pintype "input"))
    )
    (net (code "94") (name "Net-(U3B-OUT)") (class "Default")
      (node (ref "C28") (pin "2") (pinfunction "2_2") (pintype "passive"))
      (node (ref "R16") (pin "1") (pinfunction "1_1") (pintype "passive"))
      (node (ref "R17") (pin "2") (pinfunction "2_2") (pintype "passive"))
      (node (ref "U3") (pin "7") (pinfunction "OUT_7") (pintype "output"))
    )
    (net (code "95") (name "Net-(U4A--IN)") (class "Default")
      (node (ref "C35") (pin "1") (pinfunction "1_1") (pintype "passive"))
      (node (ref "R21") (pin "2") (pinfunction "2_2") (pintype "passive"))
      (node (ref "R22") (pin "2") (pinfunction "2_2") (pintype "passive"))
      (node (ref "R38") (pin "1") (pinfunction "1_1") (pintype "passive"))
      (node (ref "U4") (pin "2") (pinfunction "-IN_2") (pintype "input"))
    )
    (net (code "96") (name "Net-(U4B--IN)") (class "Default")
      (node (ref "C34") (pin "1") (pinfunction "1_1") (pintype "passive"))
      (node (ref "R19") (pin "2") (pinfunction "2_2") (pintype "passive"))
      (node (ref "R33") (pin "2") (pinfunction "2_2") (pintype "passive"))
      (node (ref "R37") (pin "1") (pinfunction "1_1") (pintype "passive"))
      (node (ref "U4") (pin "6") (pinfunction "-IN_6") (pintype "input"))
      (node (ref "VR4") (pin "1") (pinfunction "1_1") (pintype "passive"))
    )
    (net (code "97") (name "Net-(U4C--IN)") (class "Default")
      (node (ref "C37") (pin "1") (pinfunction "1_1") (pintype "passive"))
      (node (ref "R25") (pin "2") (pinfunction "2_2") (pintype "passive"))
      (node (ref "R35") (pin "2") (pinfunction "2_2") (pintype "passive"))
      (node (ref "R40") (pin "1") (pinfunction "1_1") (pintype "passive"))
      (node (ref "U4") (pin "9") (pinfunction "-IN_9") (pintype "input"))
      (node (ref "VR6") (pin "1") (pinfunction "1_1") (pintype "passive"))
    )
    (net (code "98") (name "Net-(U4D--IN)") (class "Default")
      (node (ref "C36") (pin "1") (pinfunction "1_1") (pintype "passive"))
      (node (ref "R23") (pin "2") (pinfunction "2_2") (pintype "passive"))
      (node (ref "R34") (pin "2") (pinfunction "2_2") (pintype "passive"))
      (node (ref "R39") (pin "1") (pinfunction "1_1") (pintype "passive"))
      (node (ref "U4") (pin "13") (pinfunction "-IN_13") (pintype "input"))
      (node (ref "VR5") (pin "1") (pinfunction "1_1") (pintype "passive"))
    )
    (net (code "99") (name "Net-(U5A-+IN)") (class "Default")
      (node (ref "U5") (pin "1") (pinfunction "OUT_1") (pintype "output"))
      (node (ref "U5") (pin "3") (pinfunction "+IN_3") (pintype "input"))
    )
    (net (code "100") (name "Net-(U5B--IN)") (class "Default")
      (node (ref "C38") (pin "1") (pinfunction "1_1") (pintype "passive"))
      (node (ref "R27") (pin "2") (pinfunction "2_2") (pintype "passive"))
      (node (ref "R36") (pin "2") (pinfunction "2_2") (pintype "passive"))
      (node (ref "R41") (pin "1") (pinfunction "1_1") (pintype "passive"))
      (node (ref "U5") (pin "6") (pinfunction "-IN_6") (pintype "input"))
      (node (ref "VR7") (pin "1") (pinfunction "1_1") (pintype "passive"))
    )
    (net (code "101") (name "Net-(U5C-+IN)") (class "Default")
      (node (ref "U5") (pin "10") (pinfunction "+IN_10") (pintype "input"))
      (node (ref "U5") (pin "8") (pinfunction "OUT_8") (pintype "output"))
    )
    (net (code "102") (name "Net-(U5D-+IN)") (class "Default")
      (node (ref "U5") (pin "12") (pinfunction "+IN_12") (pintype "input"))
      (node (ref "U5") (pin "14") (pinfunction "OUT_14") (pintype "output"))
    )
    (net (code "103") (name "Net-(U6A--IN)") (class "Default")
      (node (ref "C39") (pin "1") (pinfunction "1_1") (pintype "passive"))
      (node (ref "R42") (pin "2") (pinfunction "2_2") (pintype "passive"))
      (node (ref "R54") (pin "2") (pinfunction "2_2") (pintype "passive"))
      (node (ref "R58") (pin "1") (pinfunction "1_1") (pintype "passive"))
      (node (ref "U6") (pin "2") (pinfunction "-IN_2") (pintype "input"))
      (node (ref "VR8") (pin "1") (pinfunction "1_1") (pintype "passive"))
    )
    (net (code "104") (name "Net-(U6B--IN)") (class "Default")
      (node (ref "C40") (pin "1") (pinfunction "1_1") (pintype "passive"))
      (node (ref "R44") (pin "2") (pinfunction "2_2") (pintype "passive"))
      (node (ref "R55") (pin "2") (pinfunction "2_2") (pintype "passive"))
      (node (ref "R59") (pin "1") (pinfunction "1_1") (pintype "passive"))
      (node (ref "U6") (pin "6") (pinfunction "-IN_6") (pintype "input"))
      (node (ref "VR9") (pin "1") (pinfunction "1_1") (pintype "passive"))
    )
    (net (code "105") (name "Net-(U6C--IN)") (class "Default")
      (node (ref "C42") (pin "1") (pinfunction "1_1") (pintype "passive"))
      (node (ref "R48") (pin "2") (pinfunction "2_2") (pintype "passive"))
      (node (ref "R57") (pin "2") (pinfunction "2_2") (pintype "passive"))
      (node (ref "R61") (pin "1") (pinfunction "1_1") (pintype "passive"))
      (node (ref "U6") (pin "9") (pinfunction "-IN_9") (pintype "input"))
      (node (ref "VR11") (pin "1") (pinfunction "1_1") (pintype "passive"))
    )
    (net (code "106") (name "Net-(U6D--IN)") (class "Default")
      (node (ref "C41") (pin "1") (pinfunction "1_1") (pintype "passive"))
      (node (ref "R46") (pin "2") (pinfunction "2_2") (pintype "passive"))
      (node (ref "R56") (pin "2") (pinfunction "2_2") (pintype "passive"))
      (node (ref "R60") (pin "1") (pinfunction "1_1") (pintype "passive"))
      (node (ref "U6") (pin "13") (pinfunction "-IN_13") (pintype "input"))
      (node (ref "VR10") (pin "1") (pinfunction "1_1") (pintype "passive"))
    )
    (net (code "107") (name "Net-(U7A--IN)") (class "Default")
      (node (ref "R30") (pin "1") (pinfunction "1_1") (pintype "passive"))
      (node (ref "U7") (pin "2") (pinfunction "-IN_2") (pintype "input"))
      (node (ref "VR5") (pin "3") (pinfunction "3_3") (pintype "passive"))
    )
    (net (code "108") (name "Net-(U7A-OUT)") (class "Default")
      (node (ref "R30") (pin "2") (pinfunction "2_2") (pintype "passive"))
      (node (ref "R34") (pin "1") (pinfunction "1_1") (pintype "passive"))
      (node (ref "U7") (pin "1") (pinfunction "OUT_1") (pintype "output"))
    )
    (net (code "109") (name "Net-(U7B--IN)") (class "Default")
      (node (ref "R31") (pin "1") (pinfunction "1_1") (pintype "passive"))
      (node (ref "U7") (pin "6") (pinfunction "-IN_6") (pintype "input"))
      (node (ref "VR6") (pin "3") (pinfunction "3_3") (pintype "passive"))
    )
    (net (code "110") (name "Net-(U7B-OUT)") (class "Default")
      (node (ref "R31") (pin "2") (pinfunction "2_2") (pintype "passive"))
      (node (ref "R35") (pin "1") (pinfunction "1_1") (pintype "passive"))
      (node (ref "U7") (pin "7") (pinfunction "OUT_7") (pintype "output"))
    )
    (net (code "111") (name "Net-(U7C--IN)") (class "Default")
      (node (ref "R32") (pin "1") (pinfunction "1_1") (pintype "passive"))
      (node (ref "U7") (pin "9") (pinfunction "-IN_9") (pintype "input"))
      (node (ref "VR7") (pin "3") (pinfunction "3_3") (pintype "passive"))
    )
    (net (code "112") (name "Net-(U7C-OUT)") (class "Default")
      (node (ref "R32") (pin "2") (pinfunction "2_2") (pintype "passive"))
      (node (ref "R36") (pin "1") (pinfunction "1_1") (pintype "passive"))
      (node (ref "U7") (pin "8") (pinfunction "OUT_8") (pintype "output"))
    )
    (net (code "113") (name "Net-(U7D--IN)") (class "Default")
      (node (ref "R29") (pin "1") (pinfunction "1_1") (pintype "passive"))
      (node (ref "U7") (pin "13") (pinfunction "-IN_13") (pintype "input"))
      (node (ref "VR4") (pin "3") (pinfunction "3_3") (pintype "passive"))
    )
    (net (code "114") (name "Net-(U7D-OUT)") (class "Default")
      (node (ref "R29") (pin "2") (pinfunction "2_2") (pintype "passive"))
      (node (ref "R33") (pin "1") (pinfunction "1_1") (pintype "passive"))
      (node (ref "U7") (pin "14") (pinfunction "OUT_14") (pintype "output"))
    )
    (net (code "115") (name "Net-(U8A--IN)") (class "Default")
      (node (ref "R51") (pin "1") (pinfunction "1_1") (pintype "passive"))
      (node (ref "U8") (pin "2") (pinfunction "-IN_2") (pintype "input"))
      (node (ref "VR9") (pin "3") (pinfunction "3_3") (pintype "passive"))
    )
    (net (code "116") (name "Net-(U8A-OUT)") (class "Default")
      (node (ref "R51") (pin "2") (pinfunction "2_2") (pintype "passive"))
      (node (ref "R55") (pin "1") (pinfunction "1_1") (pintype "passive"))
      (node (ref "U8") (pin "1") (pinfunction "OUT_1") (pintype "output"))
    )
    (net (code "117") (name "Net-(U8B--IN)") (class "Default")
      (node (ref "R52") (pin "1") (pinfunction "1_1") (pintype "passive"))
      (node (ref "U8") (pin "6") (pinfunction "-IN_6") (pintype "input"))
      (node (ref "VR10") (pin "3") (pinfunction "3_3") (pintype "passive"))
    )
    (net (code "118") (name "Net-(U8B-OUT)") (class "Default")
      (node (ref "R52") (pin "2") (pinfunction "2_2") (pintype "passive"))
      (node (ref "R56") (pin "1") (pinfunction "1_1") (pintype "passive"))
      (node (ref "U8") (pin "7") (pinfunction "OUT_7") (pintype "output"))
    )
    (net (code "119") (name "Net-(U8C--IN)") (class "Default")
      (node (ref "R50") (pin "1") (pinfunction "1_1") (pintype "passive"))
      (node (ref "U8") (pin "9") (pinfunction "-IN_9") (pintype "input"))
      (node (ref "VR8") (pin "3") (pinfunction "3_3") (pintype "passive"))
    )
    (net (code "120") (name "Net-(U8C-OUT)") (class "Default")
      (node (ref "R50") (pin "2") (pinfunction "2_2") (pintype "passive"))
      (node (ref "R54") (pin "1") (pinfunction "1_1") (pintype "passive"))
      (node (ref "U8") (pin "8") (pinfunction "OUT_8") (pintype "output"))
    )
    (net (code "121") (name "Net-(U8D--IN)") (class "Default")
      (node (ref "R53") (pin "1") (pinfunction "1_1") (pintype "passive"))
      (node (ref "U8") (pin "13") (pinfunction "-IN_13") (pintype "input"))
      (node (ref "VR11") (pin "3") (pinfunction "3_3") (pintype "passive"))
    )
    (net (code "122") (name "Net-(U8D-OUT)") (class "Default")
      (node (ref "R53") (pin "2") (pinfunction "2_2") (pintype "passive"))
      (node (ref "R57") (pin "1") (pinfunction "1_1") (pintype "passive"))
      (node (ref "U8") (pin "14") (pinfunction "OUT_14") (pintype "output"))
    )
    (net (code "123") (name "Net-(U9-IN)") (class "Default")
      (node (ref "C51") (pin "+") (pinfunction "+_+") (pintype "passive"))
      (node (ref "R82") (pin "2") (pinfunction "2_2") (pintype "passive"))
      (node (ref "U9") (pin "3") (pinfunction "IN_3") (pintype "input"))
    )
    (net (code "124") (name "Net-(U11-PD0{slash}OSC_IN)") (class "Default")
      (node (ref "C16") (pin "2") (pinfunction "2_2") (pintype "passive"))
      (node (ref "U11") (pin "5") (pinfunction "PD0/OSC_IN_5") (pintype "bidirectional"))
      (node (ref "Y1") (pin "2") (pinfunction "2_2") (pintype "passive"))
    )
    (net (code "125") (name "Net-(U11-PD1{slash}OSC_OUT)") (class "Default")
      (node (ref "C17") (pin "2") (pinfunction "2_2") (pintype "passive"))
      (node (ref "U11") (pin "6") (pinfunction "PD1/OSC_OUT_6") (pintype "bidirectional"))
      (node (ref "Y1") (pin "1") (pinfunction "1_1") (pintype "passive"))
    )
    (net (code "126") (name "Net-(U11-VCAP_1)") (class "Default")
      (node (ref "C1") (pin "1") (pinfunction "1_1") (pintype "passive"))
      (node (ref "U11") (pin "31") (pinfunction "VCAP_1_31") (pintype "power_in"))
    )
    (net (code "127") (name "Net-(U11-VCAP_2)") (class "Default")
      (node (ref "C2") (pin "1") (pinfunction "1_1") (pintype "passive"))
      (node (ref "U11") (pin "47") (pinfunction "VCAP_2_47") (pintype "power_in"))
    )
    (net (code "128") (name "Net-(U13A-QA)") (class "Default")
      (node (ref "R67") (pin "2") (pinfunction "2_2") (pintype "passive"))
      (node (ref "U13") (pin "15") (pinfunction "QA_15") (pintype "tri_state"))
    )
    (net (code "129") (name "Net-(U13A-QB)") (class "Default")
      (node (ref "R75") (pin "2") (pinfunction "2_2") (pintype "passive"))
      (node (ref "U13") (pin "1") (pinfunction "QB_1") (pintype "tri_state"))
    )
    (net (code "130") (name "Net-(U13A-QC)") (class "Default")
      (node (ref "R68") (pin "2") (pinfunction "2_2") (pintype "passive"))
      (node (ref "U13") (pin "2") (pinfunction "QC_2") (pintype "tri_state"))
    )
    (net (code "131") (name "Net-(U13A-QD)") (class "Default")
      (node (ref "R76") (pin "2") (pinfunction "2_2") (pintype "passive"))
      (node (ref "U13") (pin "3") (pinfunction "QD_3") (pintype "tri_state"))
    )
    (net (code "132") (name "Net-(U13A-QE)") (class "Default")
      (node (ref "R69") (pin "2") (pinfunction "2_2") (pintype "passive"))
      (node (ref "U13") (pin "4") (pinfunction "QE_4") (pintype "tri_state"))
    )
    (net (code "133") (name "Net-(U13A-QF)") (class "Default")
      (node (ref "R77") (pin "2") (pinfunction "2_2") (pintype "passive"))
      (node (ref "U13") (pin "5") (pinfunction "QF_5") (pintype "tri_state"))
    )
    (net (code "134") (name "Net-(U13A-QG)") (class "Default")
      (node (ref "R70") (pin "2") (pinfunction "2_2") (pintype "passive"))
      (node (ref "U13") (pin "6") (pinfunction "QG_6") (pintype "tri_state"))
    )
    (net (code "135") (name "Net-(U13A-QH)") (class "Default")
      (node (ref "R78") (pin "2") (pinfunction "2_2") (pintype "passive"))
      (node (ref "U13") (pin "7") (pinfunction "QH_7") (pintype "tri_state"))
    )
    (net (code "136") (name "Net-(U13A-QH*)") (class "Default")
      (node (ref "U13") (pin "9") (pinfunction "QH*_9") (pintype "tri_state"))
      (node (ref "U14") (pin "14") (pinfunction "SER_14") (pintype "input"))
    )
    (net (code "137") (name "Net-(U14A-QA)") (class "Default")
      (node (ref "R71") (pin "2") (pinfunction "2_2") (pintype "passive"))
      (node (ref "U14") (pin "15") (pinfunction "QA_15") (pintype "tri_state"))
    )
    (net (code "138") (name "Net-(U14A-QB)") (class "Default")
      (node (ref "R79") (pin "2") (pinfunction "2_2") (pintype "passive"))
      (node (ref "U14") (pin "1") (pinfunction "QB_1") (pintype "tri_state"))
    )
    (net (code "139") (name "Net-(U14A-QC)") (class "Default")
      (node (ref "R72") (pin "2") (pinfunction "2_2") (pintype "passive"))
      (node (ref "U14") (pin "2") (pinfunction "QC_2") (pintype "tri_state"))
    )
    (net (code "140") (name "Net-(U14A-QD)") (class "Default")
      (node (ref "R80") (pin "2") (pinfunction "2_2") (pintype "passive"))
      (node (ref "U14") (pin "3") (pinfunction "QD_3") (pintype "tri_state"))
    )
    (net (code "141") (name "Net-(U14A-QE)") (class "Default")
      (node (ref "R73") (pin "2") (pinfunction "2_2") (pintype "passive"))
      (node (ref "U14") (pin "4") (pinfunction "QE_4") (pintype "tri_state"))
    )
    (net (code "142") (name "Net-(U14A-QF)") (class "Default")
      (node (ref "R81") (pin "2") (pinfunction "2_2") (pintype "passive"))
      (node (ref "U14") (pin "5") (pinfunction "QF_5") (pintype "tri_state"))
    )
    (net (code "143") (name "Net-(U14A-QG)") (class "Default")
      (node (ref "R74") (pin "2") (pinfunction "2_2") (pintype "passive"))
      (node (ref "U14") (pin "6") (pinfunction "QG_6") (pintype "tri_state"))
    )
    (net (code "144") (name "Net-(VR1A-1)") (class "Default")
      (node (ref "R7") (pin "1") (pinfunction "1_1") (pintype "passive"))
      (node (ref "VR1") (pin "1R1") (pinfunction "1_1R1") (pintype "passive"))
    )
    (net (code "145") (name "Net-(VR1B-1)") (class "Default")
      (node (ref "R8") (pin "1") (pinfunction "1_1") (pintype "passive"))
      (node (ref "VR1") (pin "1R2") (pinfunction "1_1R2") (pintype "passive"))
    )
    (net (code "146") (name "Net-(VR2A-3)") (class "Default")
      (node (ref "C26") (pin "-") (pinfunction "-_-") (pintype "passive"))
      (node (ref "VR2") (pin "3R1") (pinfunction "3_3R1") (pintype "passive"))
    )
    (net (code "147") (name "Net-(VR2B-3)") (class "Default")
      (node (ref "C27") (pin "-") (pinfunction "-_-") (pintype "passive"))
      (node (ref "VR2") (pin "3R2") (pinfunction "3_3R2") (pintype "passive"))
    )
    (net (code "148") (name "PITCH_CV") (class "Default")
      (node (ref "C35") (pin "2") (pinfunction "2_2") (pintype "passive"))
      (node (ref "R38") (pin "2") (pinfunction "2_2") (pintype "passive"))
      (node (ref "U11") (pin "15") (pinfunction "PA1/USART2_RTS/UART4_RX/ADC1/TIM2_CH2_15") (pintype "bidirectional"))
      (node (ref "U4") (pin "1") (pinfunction "OUT_1") (pintype "output"))
    )
    (net (code "149") (name "PITCH_POT") (class "Default")
      (node (ref "U12") (pin "2") (pinfunction "X6_2") (pintype "bidirectional"))
      (node (ref "VR15") (pin "2") (pinfunction "2_2") (pintype "passive"))
    )
    (net (code "150") (name "POSITION_CV") (class "Default")
      (node (ref "C34") (pin "2") (pinfunction "2_2") (pintype "passive"))
      (node (ref "R37") (pin "2") (pinfunction "2_2") (pintype "passive"))
      (node (ref "U11") (pin "14") (pinfunction "PA0-WKUP/USART2_CTS/UART4_TX/ADC0/TIM2_CH1_ETR_14") (pintype "bidirectional"))
      (node (ref "U4") (pin "7") (pinfunction "OUT_7") (pintype "output"))
    )
    (net (code "151") (name "POSITION_POT") (class "Default")
      (node (ref "U12") (pin "1") (pinfunction "X4_1") (pintype "bidirectional"))
      (node (ref "VR14") (pin "2") (pinfunction "2_2") (pintype "passive"))
    )
    (net (code "152") (name "RESET") (class "Default")
      (node (ref "P1") (pin "10") (pinfunction "10_10") (pintype "passive"))
      (node (ref "R1") (pin "1") (pinfunction "1_1") (pintype "passive"))
      (node (ref "SJ1") (pin "2") (pinfunction "2_2") (pintype "passive"))
      (node (ref "U11") (pin "7") (pinfunction "NRST_7") (pintype "bidirectional"))
    )
    (net (code "153") (name "REVERB_CV") (class "Default")
      (node (ref "C41") (pin "2") (pinfunction "2_2") (pintype "passive"))
      (node (ref "R60") (pin "2") (pinfunction "2_2") (pintype "passive"))
      (node (ref "U11") (pin "23") (pinfunction "PA7/SPI1_MOSI/ADC7/TIM3_CH2_23") (pintype "bidirectional"))
      (node (ref "U6") (pin "14") (pinfunction "OUT_14") (pintype "output"))
    )
    (net (code "154") (name "REVERB_POT") (class "Default")
      (node (ref "U12") (pin "15") (pinfunction "X2_15") (pintype "bidirectional"))
      (node (ref "VR13") (pin "2") (pinfunction "2_2") (pintype "passive"))
    )
    (net (code "155") (name "RIN") (class "Default")
      (node (ref "C24") (pin "+") (pinfunction "+_+") (pintype "passive"))
      (node (ref "U1") (pin "19") (pinfunction "RLINEIN_19") (pintype "bidirectional"))
    )
    (net (code "156") (name "ROUT") (class "Default")
      (node (ref "C26") (pin "+") (pinfunction "+_+") (pintype "passive"))
      (node (ref "U1") (pin "13") (pinfunction "ROUT_13") (pintype "bidirectional"))
    )
    (net (code "157") (name "SPREAD_CV") (class "Default")
      (node (ref "C39") (pin "2") (pinfunction "2_2") (pintype "passive"))
      (node (ref "R58") (pin "2") (pinfunction "2_2") (pintype "passive"))
      (node (ref "U11") (pin "21") (pinfunction "PA5/SPI1_SCK/ADC5/DAC2_21") (pintype "bidirectional"))
      (node (ref "U6") (pin "1") (pinfunction "OUT_1") (pintype "output"))
    )
    (net (code "158") (name "SPREAD_POT") (class "Default")
      (node (ref "U12") (pin "13") (pinfunction "X0_13") (pintype "bidirectional"))
      (node (ref "VR12") (pin "2") (pinfunction "2_2") (pintype "passive"))
    )
    (net (code "159") (name "SW_BUF") (class "Default")
      (node (ref "S1") (pin "3") (pinfunction "3_3") (pintype "passive"))
      (node (ref "S1") (pin "4") (pinfunction "4_4") (pintype "passive"))
      (node (ref "U11") (pin "58") (pinfunction "PB6/I2C1_SCL/TIM4_CH1/USART1_TX_58") (pintype "bidirectional"))
    )
    (net (code "160") (name "SW_CAPT") (class "Default")
      (node (ref "S2") (pin "3") (pinfunction "3_3") (pintype "passive"))
      (node (ref "S2") (pin "4") (pinfunction "4_4") (pintype "passive"))
      (node (ref "U11") (pin "59") (pinfunction "PB7/I2C1_SDA/TIM4_CH2/USART1_RX_59") (pintype "bidirectional"))
    )
    (net (code "161") (name "SW_FREEZE") (class "Default")
      (node (ref "S4") (pin "2") (pinfunction "1_2") (pintype "passive"))
      (node (ref "U11") (pin "10") (pinfunction "PC2/SPI2_MISO/ADC12_10") (pintype "bidirectional"))
    )
    (net (code "162") (name "SW_MEM") (class "Default")
      (node (ref "S3") (pin "3") (pinfunction "3_3") (pintype "passive"))
      (node (ref "S3") (pin "4") (pinfunction "4_4") (pintype "passive"))
      (node (ref "U11") (pin "57") (pinfunction "PB5/I2C1_SMBA/SPI1_MOSI/SPI3_MOSI/I2S3_SD_57") (pintype "bidirectional"))
    )
    (net (code "163") (name "TEXTURE_CV") (class "Default")
      (node (ref "C37") (pin "2") (pinfunction "2_2") (pintype "passive"))
      (node (ref "R40") (pin "2") (pinfunction "2_2") (pintype "passive"))
      (node (ref "U11") (pin "17") (pinfunction "PA3/USART2_RX/ADC3/TIM2_CH4_17") (pintype "bidirectional"))
      (node (ref "U4") (pin "8") (pinfunction "OUT_8") (pintype "output"))
    )
    (net (code "164") (name "TEXTURE_POT") (class "Default")
      (node (ref "U12") (pin "5") (pinfunction "X5_5") (pintype "bidirectional"))
      (node (ref "VR18") (pin "2") (pinfunction "2_2") (pintype "passive"))
    )
    (net (code "165") (name "VBAT") (class "Default")
      (node (ref "U11") (pin "1") (pinfunction "VBAT_1") (pintype "power_in"))
    )
    (net (code "166") (name "VCC") (class "Default")
      (node (ref "C30") (pin "1") (pinfunction "1_1") (pintype "passive"))
      (node (ref "C32") (pin "1") (pinfunction "1_1") (pintype "passive"))
      (node (ref "C54") (pin "+") (pinfunction "+_+") (pintype "passive"))
      (node (ref "C60") (pin "1") (pinfunction "1_1") (pintype "passive"))
      (node (ref "C63") (pin "1") (pinfunction "1_1") (pintype "passive"))
      (node (ref "P2") (pin "3") (pinfunction "3_3") (pintype "passive"))
      (node (ref "U2") (pin "8") (pinfunction "V+_8") (pintype "power_in"))
      (node (ref "U3") (pin "8") (pinfunction "V+_8") (pintype "power_in"))
      (node (ref "U7") (pin "4") (pinfunction "V+_4") (pintype "power_in"))
      (node (ref "U8") (pin "4") (pinfunction "V+_4") (pintype "power_in"))
    )
    (net (code "167") (name "VEE") (class "Default")
      (node (ref "C31") (pin "2") (pinfunction "2_2") (pintype "passive"))
      (node (ref "C33") (pin "2") (pinfunction "2_2") (pintype "passive"))
      (node (ref "C55") (pin "-") (pinfunction "-_-") (pintype "passive"))
      (node (ref "C61") (pin "2") (pinfunction "2_2") (pintype "passive"))
      (node (ref "C62") (pin "2") (pinfunction "2_2") (pintype "passive"))
      (node (ref "P2") (pin "2") (pinfunction "2_2") (pintype "passive"))
      (node (ref "R83") (pin "1") (pinfunction "1_1") (pintype "passive"))
      (node (ref "U2") (pin "4") (pinfunction "V-_4") (pintype "power_in"))
      (node (ref "U3") (pin "4") (pinfunction "V-_4") (pintype "power_in"))
      (node (ref "U7") (pin "11") (pinfunction "V-_11") (pintype "power_in"))
      (node (ref "U8") (pin "11") (pinfunction "V-_11") (pintype "power_in"))
    )
    (net (code "168") (name "unconnected-(P1-Pad7)") (class "Default")
      (node (ref "P1") (pin "7") (pinfunction "7_7") (pintype "passive"))
    )
    (net (code "169") (name "unconnected-(P2-Pad4)") (class "Default")
      (node (ref "P2") (pin "4") (pinfunction "4_4") (pintype "passive"))
    )
    (net (code "170") (name "unconnected-(P2-Pad6)") (class "Default")
      (node (ref "P2") (pin "6") (pinfunction "6_6") (pintype "passive"))
    )
    (net (code "171") (name "unconnected-(U1-CLKOUT-Pad2)") (class "Default")
      (node (ref "U1") (pin "2") (pinfunction "CLKOUT_2") (pintype "bidirectional"))
    )
    (net (code "172") (name "unconnected-(U1-LHPOUT-Pad9)") (class "Default")
      (node (ref "U1") (pin "9") (pinfunction "LHPOUT_9") (pintype "bidirectional"))
    )
    (net (code "173") (name "unconnected-(U1-MICBIAS-Pad17)") (class "Default")
      (node (ref "U1") (pin "17") (pinfunction "MICBIAS_17") (pintype "bidirectional"))
    )
    (net (code "174") (name "unconnected-(U1-MICIN-Pad18)") (class "Default")
      (node (ref "U1") (pin "18") (pinfunction "MICIN_18") (pintype "bidirectional"))
    )
    (net (code "175") (name "unconnected-(U1-RHPOUT-Pad10)") (class "Default")
      (node (ref "U1") (pin "10") (pinfunction "RHPOUT_10") (pintype "bidirectional"))
    )
    (net (code "176") (name "unconnected-(U11-PA8{slash}USART1_CK{slash}TIM1_CH1{slash}MCO-Pad41)") (class "Default")
      (node (ref "U11") (pin "41") (pinfunction "PA8/USART1_CK/TIM1_CH1/MCO_41") (pintype "bidirectional"))
    )
    (net (code "177") (name "unconnected-(U11-PA9{slash}USART1_TX{slash}TIM1_CH2-Pad42)") (class "Default")
      (node (ref "U11") (pin "42") (pinfunction "PA9/USART1_TX/TIM1_CH2_42") (pintype "bidirectional"))
    )
    (net (code "178") (name "unconnected-(U11-PA10{slash}USART1_RX{slash}TIM1_CH3-Pad43)") (class "Default")
      (node (ref "U11") (pin "43") (pinfunction "PA10/USART1_RX/TIM1_CH3_43") (pintype "bidirectional"))
    )
    (net (code "179") (name "unconnected-(U11-PA11{slash}USART1_CTS{slash}CANRX{slash}USBDM{slash}TIM1_CH4-Pad44)") (class "Default")
      (node (ref "U11") (pin "44") (pinfunction "PA11/USART1_CTS/CANRX/USBDM/TIM1_CH4_44") (pintype "bidirectional"))
    )
    (net (code "180") (name "unconnected-(U11-PA12{slash}USART1_RTS{slash}CANTX{slash}USBDP{slash}TIM1_ETR-Pad45)") (class "Default")
      (node (ref "U11") (pin "45") (pinfunction "PA12/USART1_RTS/CANTX/USBDP/TIM1_ETR_45") (pintype "bidirectional"))
    )
    (net (code "181") (name "unconnected-(U11-PB8{slash}TIM4_CH3{slash}I2C1_SCL-Pad61)") (class "Default")
      (node (ref "U11") (pin "61") (pinfunction "PB8/TIM4_CH3/I2C1_SCL_61") (pintype "bidirectional"))
    )
    (net (code "182") (name "unconnected-(U11-PB9{slash}SPI2_NSS{slash}I2S2_WS{slash}I2C1_SDA{slash}TIM4_CH4-Pad62)") (class "Default")
      (node (ref "U11") (pin "62") (pinfunction "PB9/SPI2_NSS/I2S2_WS/I2C1_SDA/TIM4_CH4_62") (pintype "bidirectional"))
    )
    (net (code "183") (name "unconnected-(U11-PC5{slash}ADC15-Pad25)") (class "Default")
      (node (ref "U11") (pin "25") (pinfunction "PC5/ADC15_25") (pintype "bidirectional"))
    )
    (net (code "184") (name "unconnected-(U11-PC13-TAMPER-RTC-Pad2)") (class "Default")
      (node (ref "U11") (pin "2") (pinfunction "PC13-TAMPER-RTC_2") (pintype "bidirectional"))
    )
    (net (code "185") (name "unconnected-(U11-PC14{slash}OSC32_IN-Pad3)") (class "Default")
      (node (ref "U11") (pin "3") (pinfunction "PC14/OSC32_IN_3") (pintype "bidirectional"))
    )
    (net (code "186") (name "unconnected-(U11-PC15{slash}OSC_OUT-Pad4)") (class "Default")
      (node (ref "U11") (pin "4") (pinfunction "PC15/OSC_OUT_4") (pintype "bidirectional"))
    )
    (net (code "187") (name "unconnected-(U11-PD2{slash}TIM3-ETR-Pad54)") (class "Default")
      (node (ref "U11") (pin "54") (pinfunction "PD2/TIM3-ETR_54") (pintype "bidirectional"))
    )
    (net (code "188") (name "unconnected-(U14A-QH*-Pad9)") (class "Default")
      (node (ref "U14") (pin "9") (pinfunction "QH*_9") (pintype "tri_state"))
    )
    (net (code "189") (name "unconnected-(U14A-QH-Pad7)") (class "Default")
      (node (ref "U14") (pin "7") (pinfunction "QH_7") (pintype "tri_state"))
    )
  )
)
